# ZynQ7xxx.net
KiCad netlist of a schematic drawn in Altium Designer
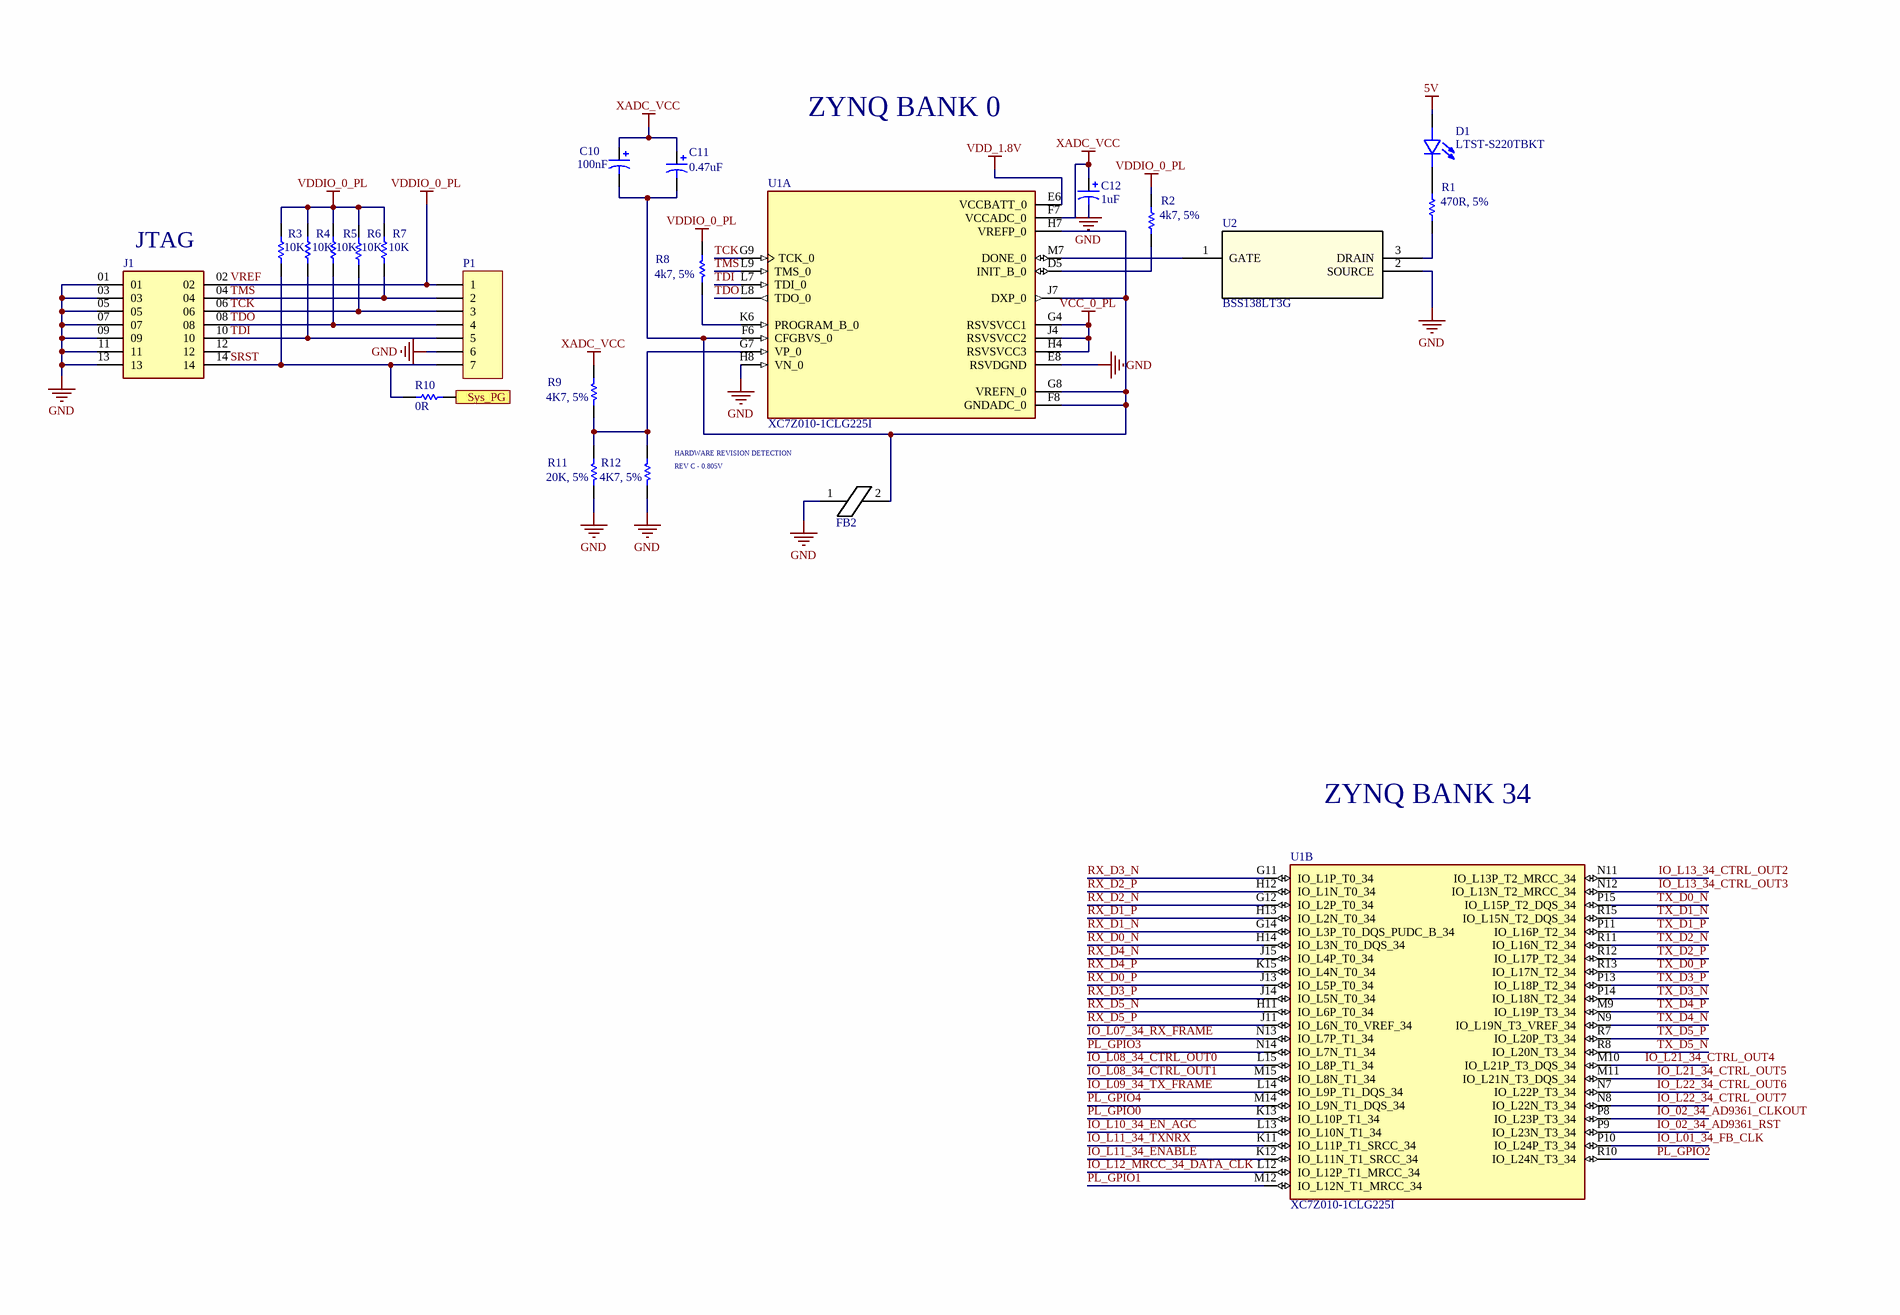
[diagram p0: ZynQ7xxx.SchDoc, top left]
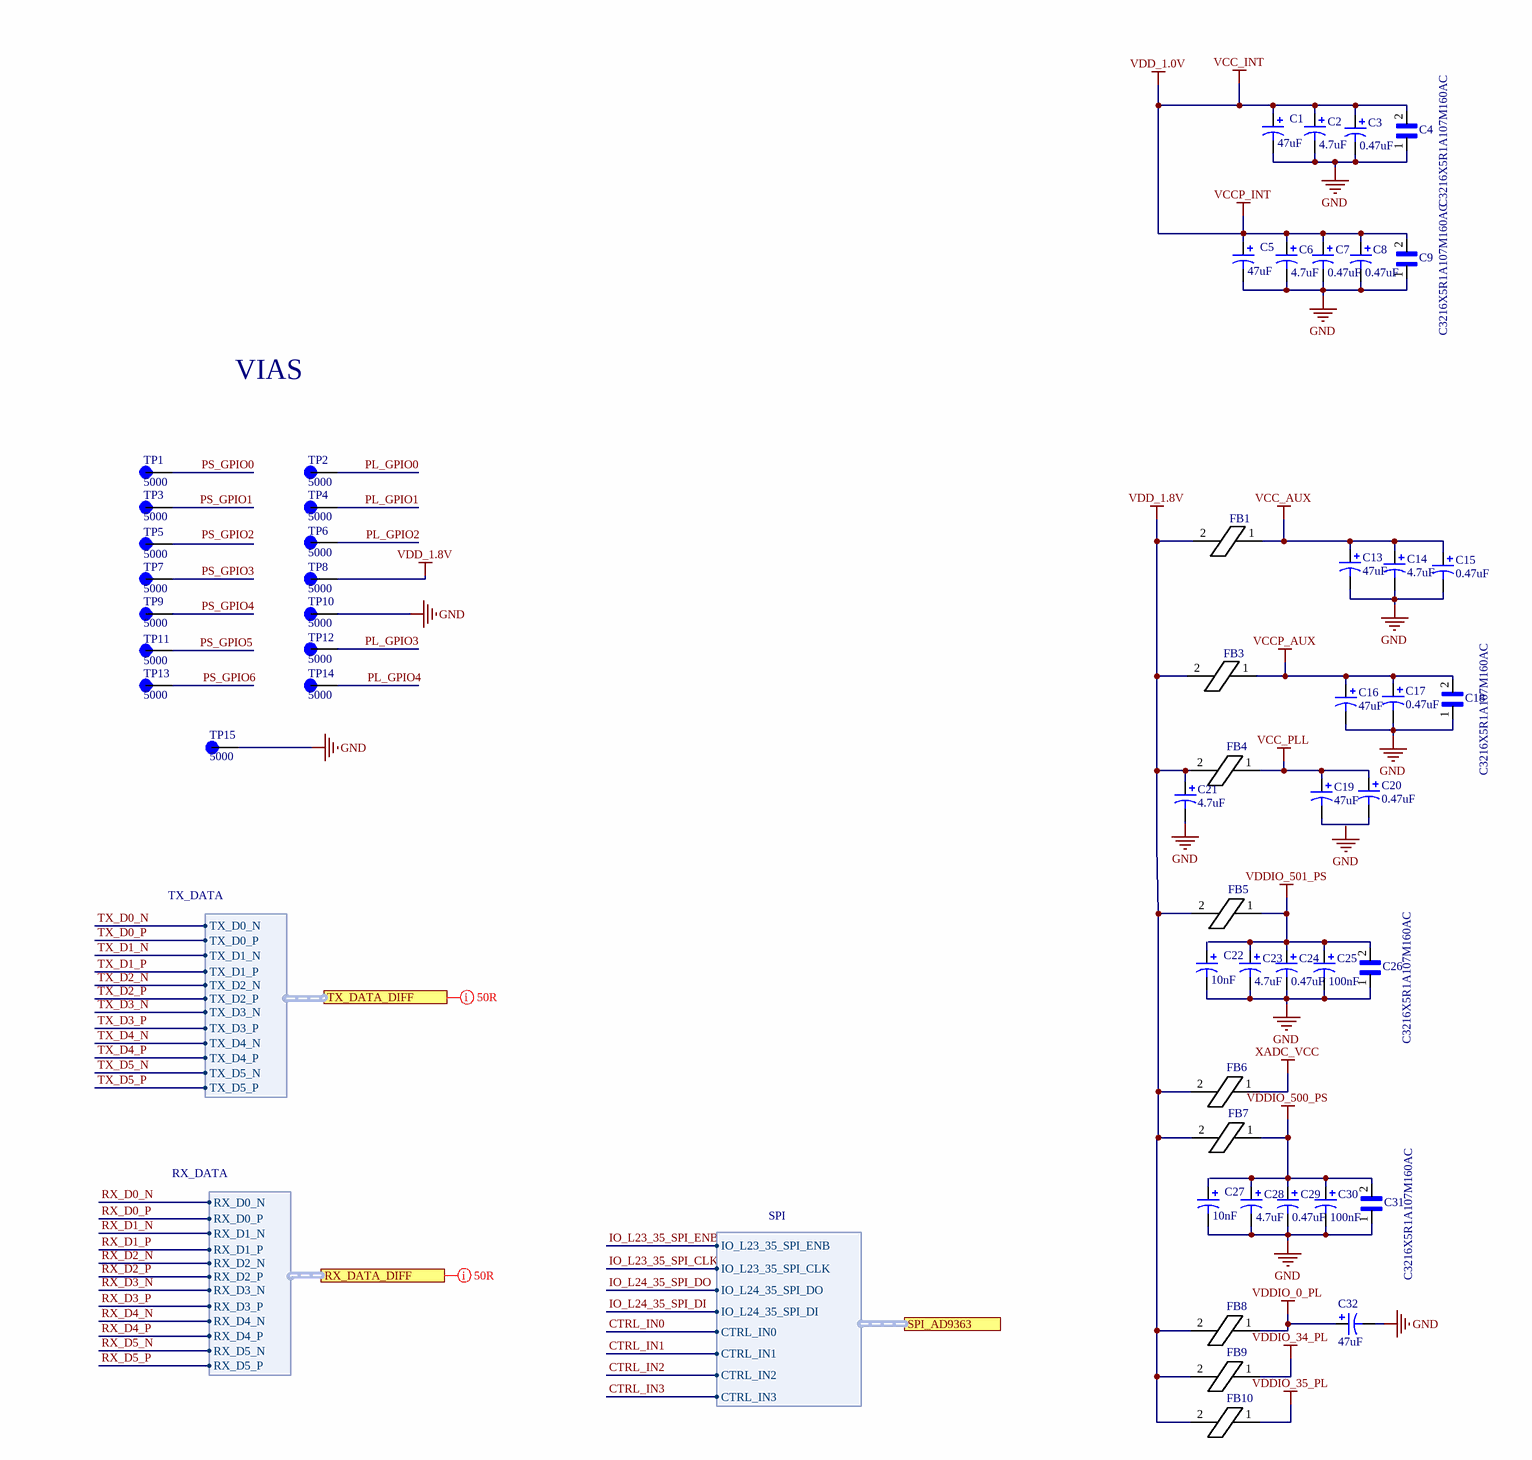
[diagram p1: ZynQ7xxx.SchDoc, top right]
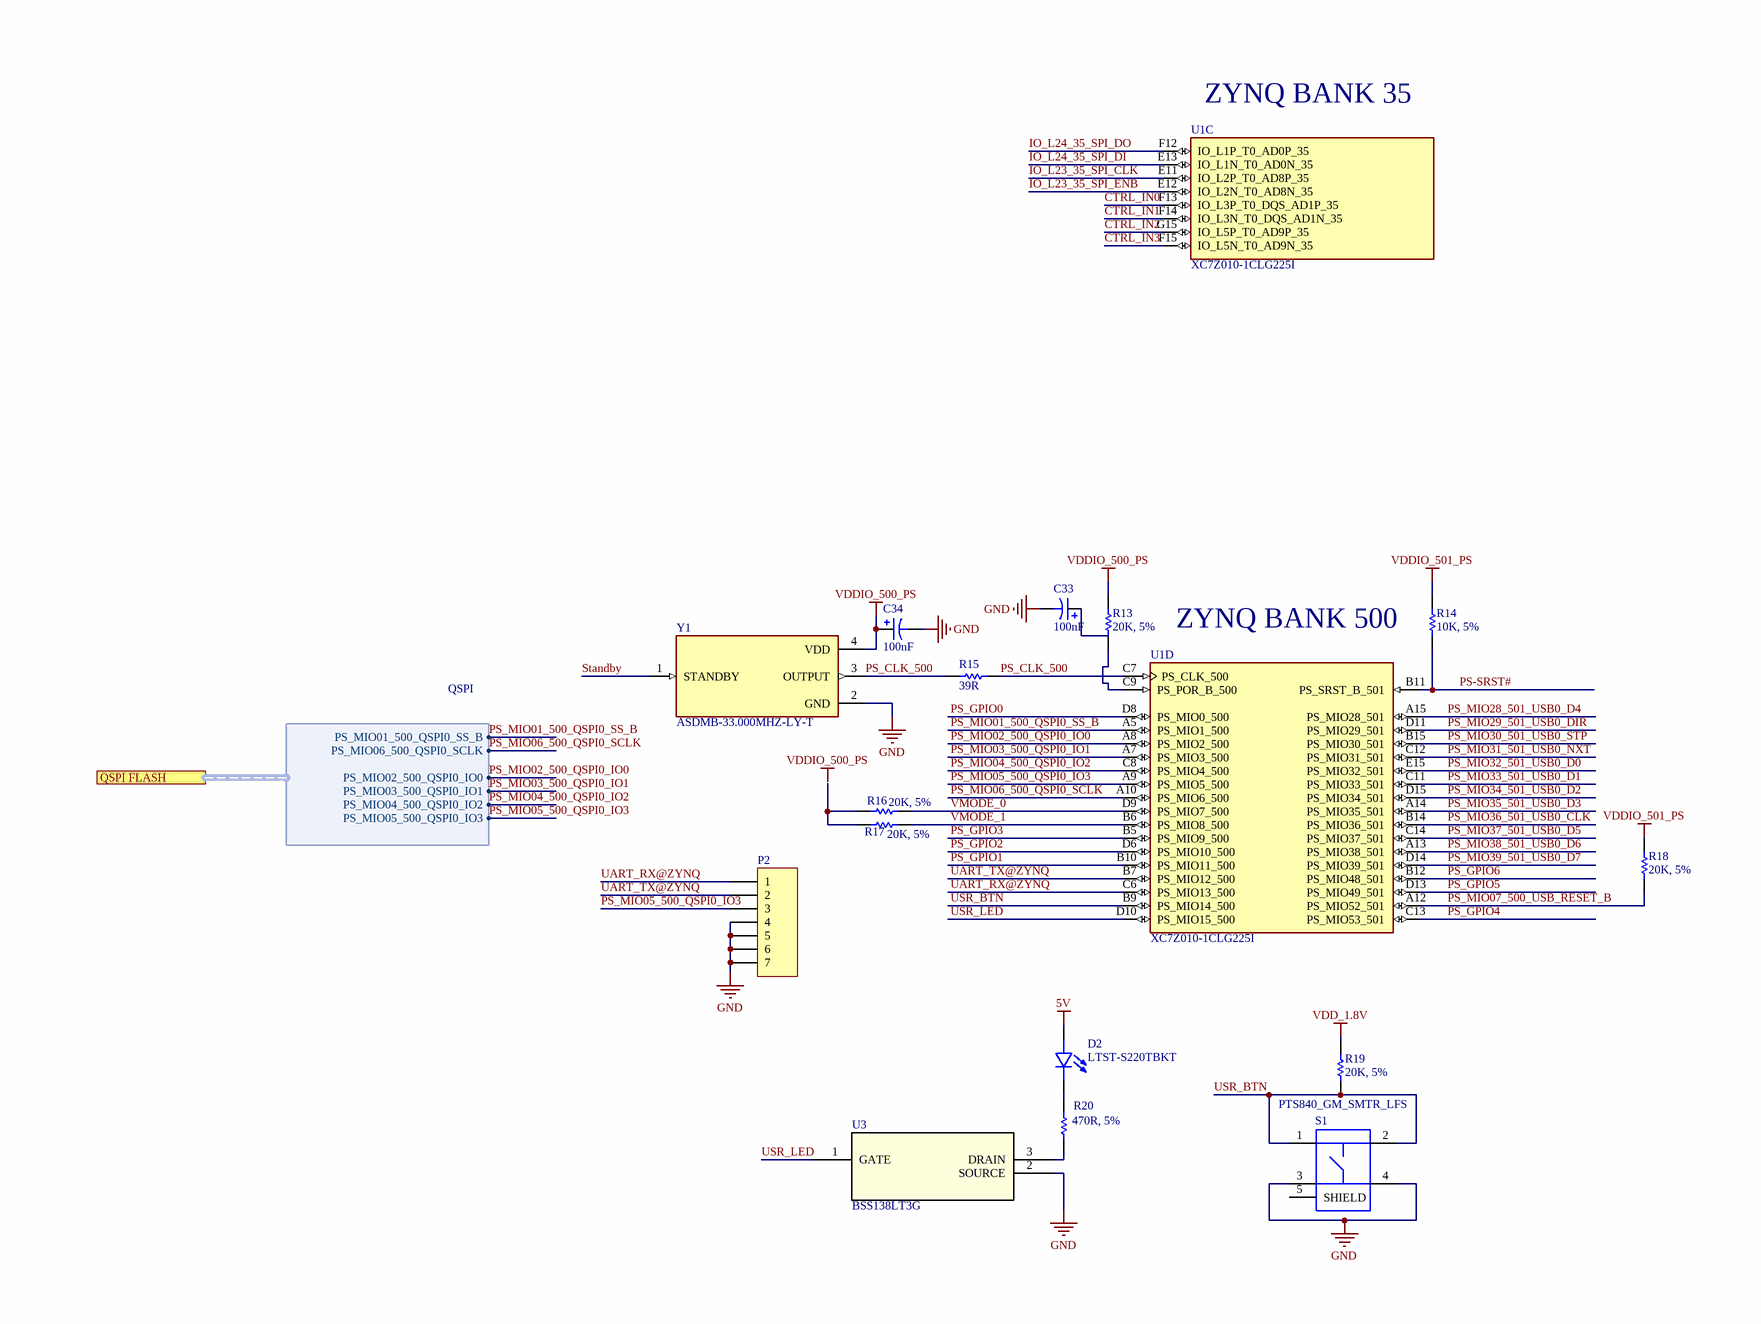
[diagram p2: ZynQ7xxx.SchDoc, bottom left]
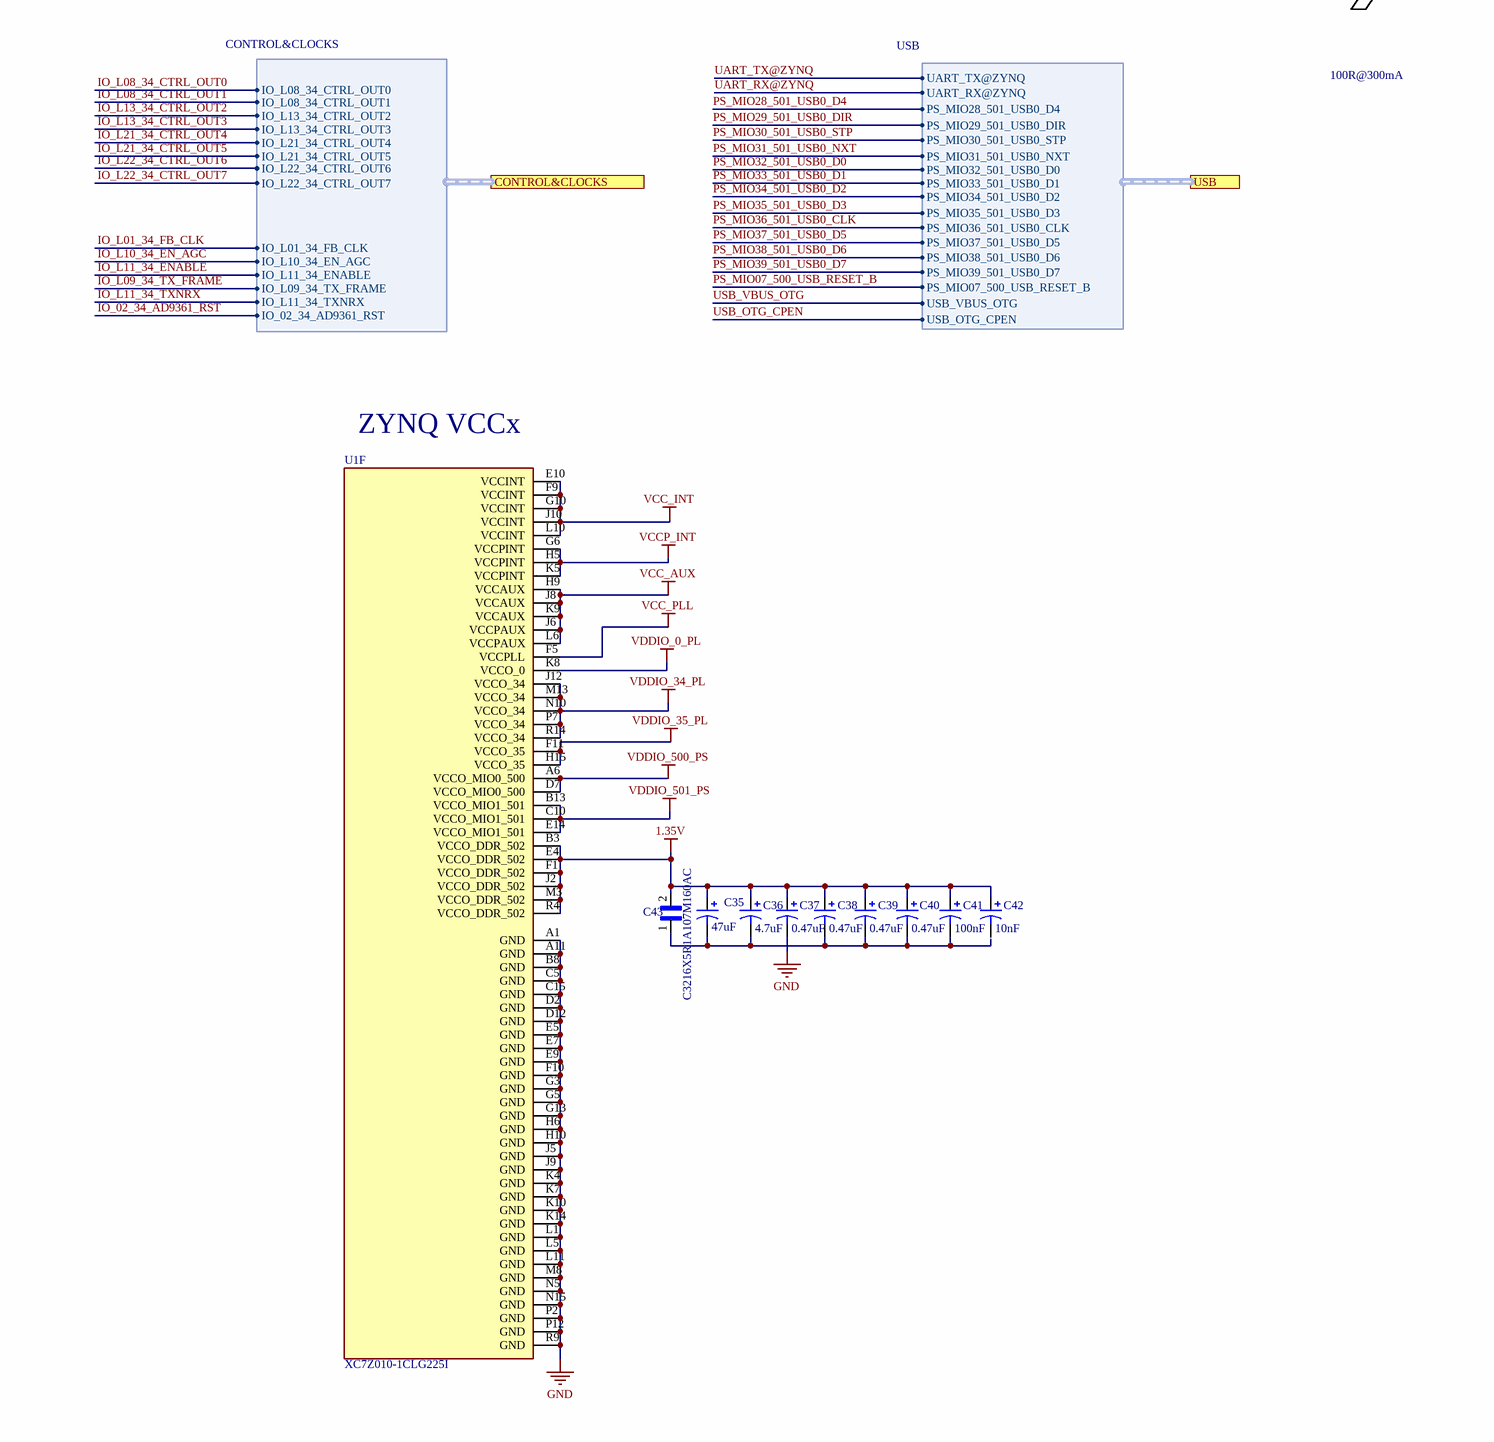
[diagram p3: ZynQ7xxx.SchDoc, bottom right]

(export (version "E")
  (design (tool "Eeschema 10.0.6"))
  (components
    (comp (ref "C1")
      (value "47uF")
      (footprint "C0805")
      (description "Polarized Capacitor (Surface Mount)")
      (fields (field (name "Comment") "Cap Pol3") (field (name "PUBLISHER") "Altium Limited"))
      (libsource (lib "Miscellaneous Devices") (part "Cap Pol3"))
    )
    (comp (ref "C2")
      (value "4.7uF")
      (footprint "C0805")
      (description "Polarized Capacitor (Surface Mount)")
      (fields (field (name "Comment") "Cap Pol3") (field (name "PUBLISHER") "Altium Limited"))
      (libsource (lib "Miscellaneous Devices") (part "Cap Pol3"))
    )
    (comp (ref "C3")
      (value "0.47uF")
      (footprint "C0805")
      (description "Polarized Capacitor (Surface Mount)")
      (fields (field (name "Comment") "Cap Pol3") (field (name "PUBLISHER") "Altium Limited"))
      (libsource (lib "Miscellaneous Devices") (part "Cap Pol3"))
    )
    (comp (ref "C4")
      (value "C3216X5R1A107M160AC")
      (footprint "CAPC3216X190N")
      (description "100 ÂµF Â±20% 10V Ceramic Capacitor X5R 1206 (3216 Metric)")
      (fields (field (name "MF") "TDK") (field (name "DIGI-KEY_PART_NUMBER") "445-6007-1-ND"))
      (libsource (lib "C3216X5R1A107M160AC") (part "C3216X5R1A107M160AC"))
    )
    (comp (ref "C5")
      (value "47uF")
      (footprint "C0805")
      (description "Polarized Capacitor (Surface Mount)")
      (fields (field (name "Comment") "Cap Pol3") (field (name "PUBLISHER") "Altium Limited"))
      (libsource (lib "Miscellaneous Devices") (part "Cap Pol3"))
    )
    (comp (ref "C6")
      (value "4.7uF")
      (footprint "C0805")
      (description "Polarized Capacitor (Surface Mount)")
      (fields (field (name "Comment") "Cap Pol3") (field (name "PUBLISHER") "Altium Limited"))
      (libsource (lib "Miscellaneous Devices") (part "Cap Pol3"))
    )
    (comp (ref "C7")
      (value "0.47uF")
      (footprint "C0805")
      (description "Polarized Capacitor (Surface Mount)")
      (fields (field (name "Comment") "Cap Pol3") (field (name "PUBLISHER") "Altium Limited"))
      (libsource (lib "Miscellaneous Devices") (part "Cap Pol3"))
    )
    (comp (ref "C8")
      (value "0.47uF")
      (footprint "C0805")
      (description "Polarized Capacitor (Surface Mount)")
      (fields (field (name "Comment") "Cap Pol3") (field (name "PUBLISHER") "Altium Limited"))
      (libsource (lib "Miscellaneous Devices") (part "Cap Pol3"))
    )
    (comp (ref "C9")
      (value "C3216X5R1A107M160AC")
      (footprint "CAPC3216X190N")
      (description "100 ÂµF Â±20% 10V Ceramic Capacitor X5R 1206 (3216 Metric)")
      (fields (field (name "MF") "TDK") (field (name "DIGI-KEY_PART_NUMBER") "445-6007-1-ND"))
      (libsource (lib "C3216X5R1A107M160AC") (part "C3216X5R1A107M160AC"))
    )
    (comp (ref "C10")
      (value "100nF")
      (footprint "C0805")
      (description "Polarized Capacitor (Surface Mount)")
      (fields (field (name "Comment") "Cap Pol3") (field (name "PUBLISHER") "Altium Limited"))
      (libsource (lib "Miscellaneous Devices") (part "Cap Pol3"))
    )
    (comp (ref "C11")
      (value "0.47uF")
      (footprint "C0805")
      (description "Polarized Capacitor (Surface Mount)")
      (fields (field (name "Comment") "Cap Pol3") (field (name "PUBLISHER") "Altium Limited"))
      (libsource (lib "Miscellaneous Devices") (part "Cap Pol3"))
    )
    (comp (ref "C12")
      (value "1uF")
      (footprint "C0805")
      (description "Polarized Capacitor (Surface Mount)")
      (fields (field (name "Comment") "Cap Pol3") (field (name "PUBLISHER") "Altium Limited"))
      (libsource (lib "Miscellaneous Devices") (part "Cap Pol3"))
    )
    (comp (ref "C13")
      (value "47uF")
      (footprint "C0805")
      (description "Polarized Capacitor (Surface Mount)")
      (fields (field (name "Comment") "Cap Pol3") (field (name "PUBLISHER") "Altium Limited"))
      (libsource (lib "Miscellaneous Devices") (part "Cap Pol3"))
    )
    (comp (ref "C14")
      (value "4.7uF")
      (footprint "C0805")
      (description "Polarized Capacitor (Surface Mount)")
      (fields (field (name "Comment") "Cap Pol3") (field (name "PUBLISHER") "Altium Limited"))
      (libsource (lib "Miscellaneous Devices") (part "Cap Pol3"))
    )
    (comp (ref "C15")
      (value "0.47uF")
      (footprint "C0805")
      (description "Polarized Capacitor (Surface Mount)")
      (fields (field (name "Comment") "Cap Pol3") (field (name "PUBLISHER") "Altium Limited"))
      (libsource (lib "Miscellaneous Devices") (part "Cap Pol3"))
    )
    (comp (ref "C16")
      (value "47uF")
      (footprint "C0805")
      (description "Polarized Capacitor (Surface Mount)")
      (fields (field (name "Comment") "Cap Pol3") (field (name "PUBLISHER") "Altium Limited"))
      (libsource (lib "Miscellaneous Devices") (part "Cap Pol3"))
    )
    (comp (ref "C17")
      (value "0.47uF")
      (footprint "C0805")
      (description "Polarized Capacitor (Surface Mount)")
      (fields (field (name "Comment") "Cap Pol3") (field (name "PUBLISHER") "Altium Limited"))
      (libsource (lib "Miscellaneous Devices") (part "Cap Pol3"))
    )
    (comp (ref "C18")
      (value "C3216X5R1A107M160AC")
      (footprint "CAPC3216X190N")
      (description "100 ÂµF Â±20% 10V Ceramic Capacitor X5R 1206 (3216 Metric)")
      (fields (field (name "MF") "TDK") (field (name "DIGI-KEY_PART_NUMBER") "445-6007-1-ND"))
      (libsource (lib "C3216X5R1A107M160AC") (part "C3216X5R1A107M160AC"))
    )
    (comp (ref "C19")
      (value "47uF")
      (footprint "C0805")
      (description "Polarized Capacitor (Surface Mount)")
      (fields (field (name "Comment") "Cap Pol3") (field (name "PUBLISHER") "Altium Limited"))
      (libsource (lib "Miscellaneous Devices") (part "Cap Pol3"))
    )
    (comp (ref "C20")
      (value "0.47uF")
      (footprint "C0805")
      (description "Polarized Capacitor (Surface Mount)")
      (fields (field (name "Comment") "Cap Pol3") (field (name "PUBLISHER") "Altium Limited"))
      (libsource (lib "Miscellaneous Devices") (part "Cap Pol3"))
    )
    (comp (ref "C21")
      (value "4.7uF")
      (footprint "C0805")
      (description "Polarized Capacitor (Surface Mount)")
      (fields (field (name "Comment") "Cap Pol3") (field (name "PUBLISHER") "Altium Limited"))
      (libsource (lib "Miscellaneous Devices") (part "Cap Pol3"))
    )
    (comp (ref "C22")
      (value "10nF")
      (footprint "C0805")
      (description "Polarized Capacitor (Surface Mount)")
      (fields (field (name "Comment") "Cap Pol3") (field (name "PUBLISHER") "Altium Limited"))
      (libsource (lib "Miscellaneous Devices") (part "Cap Pol3"))
    )
    (comp (ref "C23")
      (value "4.7uF")
      (footprint "C0805")
      (description "Polarized Capacitor (Surface Mount)")
      (fields (field (name "Comment") "Cap Pol3") (field (name "PUBLISHER") "Altium Limited"))
      (libsource (lib "Miscellaneous Devices") (part "Cap Pol3"))
    )
    (comp (ref "C24")
      (value "0.47uF")
      (footprint "C0805")
      (description "Polarized Capacitor (Surface Mount)")
      (fields (field (name "Comment") "Cap Pol3") (field (name "PUBLISHER") "Altium Limited"))
      (libsource (lib "Miscellaneous Devices") (part "Cap Pol3"))
    )
    (comp (ref "C25")
      (value "100nF")
      (footprint "C0805")
      (description "Polarized Capacitor (Surface Mount)")
      (fields (field (name "Comment") "Cap Pol3") (field (name "PUBLISHER") "Altium Limited"))
      (libsource (lib "Miscellaneous Devices") (part "Cap Pol3"))
    )
    (comp (ref "C26")
      (value "C3216X5R1A107M160AC")
      (footprint "CAPC3216X190N")
      (description "100 ÂµF Â±20% 10V Ceramic Capacitor X5R 1206 (3216 Metric)")
      (fields (field (name "MF") "TDK") (field (name "DIGI-KEY_PART_NUMBER") "445-6007-1-ND"))
      (libsource (lib "C3216X5R1A107M160AC") (part "C3216X5R1A107M160AC"))
    )
    (comp (ref "C27")
      (value "10nF")
      (footprint "C0805")
      (description "Polarized Capacitor (Surface Mount)")
      (fields (field (name "Comment") "Cap Pol3") (field (name "PUBLISHER") "Altium Limited"))
      (libsource (lib "Miscellaneous Devices") (part "Cap Pol3"))
    )
    (comp (ref "C28")
      (value "4.7uF")
      (footprint "C0805")
      (description "Polarized Capacitor (Surface Mount)")
      (fields (field (name "Comment") "Cap Pol3") (field (name "PUBLISHER") "Altium Limited"))
      (libsource (lib "Miscellaneous Devices") (part "Cap Pol3"))
    )
    (comp (ref "C29")
      (value "0.47uF")
      (footprint "C0805")
      (description "Polarized Capacitor (Surface Mount)")
      (fields (field (name "Comment") "Cap Pol3") (field (name "PUBLISHER") "Altium Limited"))
      (libsource (lib "Miscellaneous Devices") (part "Cap Pol3"))
    )
    (comp (ref "C30")
      (value "100nF")
      (footprint "C0805")
      (description "Polarized Capacitor (Surface Mount)")
      (fields (field (name "Comment") "Cap Pol3") (field (name "PUBLISHER") "Altium Limited"))
      (libsource (lib "Miscellaneous Devices") (part "Cap Pol3"))
    )
    (comp (ref "C31")
      (value "C3216X5R1A107M160AC")
      (footprint "CAPC3216X190N")
      (description "100 ÂµF Â±20% 10V Ceramic Capacitor X5R 1206 (3216 Metric)")
      (fields (field (name "MF") "TDK") (field (name "DIGI-KEY_PART_NUMBER") "445-6007-1-ND"))
      (libsource (lib "C3216X5R1A107M160AC") (part "C3216X5R1A107M160AC"))
    )
    (comp (ref "C32")
      (value "47uF")
      (footprint "C0805")
      (description "Polarized Capacitor (Surface Mount)")
      (fields (field (name "Comment") "Cap Pol3") (field (name "PUBLISHER") "Altium Limited"))
      (libsource (lib "Miscellaneous Devices") (part "Cap Pol3"))
    )
    (comp (ref "C33")
      (value "100nF")
      (footprint "C0805")
      (description "Polarized Capacitor (Surface Mount)")
      (fields (field (name "Comment") "Cap Pol3") (field (name "PUBLISHER") "Altium Limited"))
      (libsource (lib "Miscellaneous Devices") (part "Cap Pol3"))
    )
    (comp (ref "C34")
      (value "100nF")
      (footprint "C0805")
      (description "Polarized Capacitor (Surface Mount)")
      (fields (field (name "Comment") "Cap Pol3") (field (name "PUBLISHER") "Altium Limited"))
      (libsource (lib "Miscellaneous Devices") (part "Cap Pol3"))
    )
    (comp (ref "C35")
      (value "47uF")
      (footprint "C0805")
      (description "Polarized Capacitor (Surface Mount)")
      (fields (field (name "Comment") "Cap Pol3") (field (name "PUBLISHER") "Altium Limited"))
      (libsource (lib "Miscellaneous Devices") (part "Cap Pol3"))
    )
    (comp (ref "C36")
      (value "4.7uF")
      (footprint "C0805")
      (description "Polarized Capacitor (Surface Mount)")
      (fields (field (name "Comment") "Cap Pol3") (field (name "PUBLISHER") "Altium Limited"))
      (libsource (lib "Miscellaneous Devices") (part "Cap Pol3"))
    )
    (comp (ref "C37")
      (value "0.47uF")
      (footprint "C0805")
      (description "Polarized Capacitor (Surface Mount)")
      (fields (field (name "Comment") "Cap Pol3") (field (name "PUBLISHER") "Altium Limited"))
      (libsource (lib "Miscellaneous Devices") (part "Cap Pol3"))
    )
    (comp (ref "C38")
      (value "0.47uF")
      (footprint "C0805")
      (description "Polarized Capacitor (Surface Mount)")
      (fields (field (name "Comment") "Cap Pol3") (field (name "PUBLISHER") "Altium Limited"))
      (libsource (lib "Miscellaneous Devices") (part "Cap Pol3"))
    )
    (comp (ref "C39")
      (value "0.47uF")
      (footprint "C0805")
      (description "Polarized Capacitor (Surface Mount)")
      (fields (field (name "Comment") "Cap Pol3") (field (name "PUBLISHER") "Altium Limited"))
      (libsource (lib "Miscellaneous Devices") (part "Cap Pol3"))
    )
    (comp (ref "C40")
      (value "0.47uF")
      (footprint "C0805")
      (description "Polarized Capacitor (Surface Mount)")
      (fields (field (name "Comment") "Cap Pol3") (field (name "PUBLISHER") "Altium Limited"))
      (libsource (lib "Miscellaneous Devices") (part "Cap Pol3"))
    )
    (comp (ref "C41")
      (value "100nF")
      (footprint "C0805")
      (description "Polarized Capacitor (Surface Mount)")
      (fields (field (name "Comment") "Cap Pol3") (field (name "PUBLISHER") "Altium Limited"))
      (libsource (lib "Miscellaneous Devices") (part "Cap Pol3"))
    )
    (comp (ref "C42")
      (value "10nF")
      (footprint "C0805")
      (description "Polarized Capacitor (Surface Mount)")
      (fields (field (name "Comment") "Cap Pol3") (field (name "PUBLISHER") "Altium Limited"))
      (libsource (lib "Miscellaneous Devices") (part "Cap Pol3"))
    )
    (comp (ref "C43")
      (value "C3216X5R1A107M160AC")
      (footprint "CAPC3216X190N")
      (description "100 ÂµF Â±20% 10V Ceramic Capacitor X5R 1206 (3216 Metric)")
      (fields (field (name "MF") "TDK") (field (name "DIGI-KEY_PART_NUMBER") "445-6007-1-ND"))
      (libsource (lib "C3216X5R1A107M160AC") (part "C3216X5R1A107M160AC"))
    )
    (comp (ref "D1")
      (value "LTST-S220TBKT")
      (footprint "LED_LTST-S220TBKT")
      (libsource (lib "LTST-S220TBKT") (part "LTST-S220TBKT"))
    )
    (comp (ref "D2")
      (value "LTST-S220TBKT")
      (footprint "LED_LTST-S220TBKT")
      (libsource (lib "LTST-S220TBKT") (part "LTST-S220TBKT"))
    )
    (comp (ref "FB1")
      (value "FERRITA")
      (footprint "0805R")
      (libsource (lib "lib_protel_HC") (part "FERRITA"))
    )
    (comp (ref "FB2")
      (value "FERRITA")
      (footprint "0805R")
      (libsource (lib "lib_protel_HC") (part "FERRITA"))
    )
    (comp (ref "FB3")
      (value "FERRITA")
      (footprint "0805R")
      (libsource (lib "lib_protel_HC") (part "FERRITA"))
    )
    (comp (ref "FB4")
      (value "FERRITA")
      (footprint "0805R")
      (libsource (lib "lib_protel_HC") (part "FERRITA"))
    )
    (comp (ref "FB5")
      (value "FERRITA")
      (footprint "0805R")
      (libsource (lib "lib_protel_HC") (part "FERRITA"))
    )
    (comp (ref "FB6")
      (value "FERRITA")
      (footprint "0805R")
      (libsource (lib "lib_protel_HC") (part "FERRITA"))
    )
    (comp (ref "FB7")
      (value "FERRITA")
      (footprint "0805R")
      (libsource (lib "lib_protel_HC") (part "FERRITA"))
    )
    (comp (ref "FB8")
      (value "FERRITA")
      (footprint "0805R")
      (libsource (lib "lib_protel_HC") (part "FERRITA"))
    )
    (comp (ref "FB9")
      (value "FERRITA")
      (footprint "0805R")
      (libsource (lib "lib_protel_HC") (part "FERRITA"))
    )
    (comp (ref "FB10")
      (value "FERRITA")
      (footprint "0805R")
      (libsource (lib "lib_protel_HC") (part "FERRITA"))
    )
    (comp (ref "J1")
      (value "MTMM-107-03-G-D-190")
      (footprint "SAMTEC_MTMM-107-03-G-D-190")
      (libsource (lib "MTMM-107-03-G-D-190") (part "MTMM-107-03-G-D-190"))
    )
    (comp (ref "P1")
      (value "Header 7")
      (footprint "HDR1X7")
      (description "Header, 7-Pin")
      (fields (field (name "PUBLISHER") "Altium Limited"))
      (libsource (lib "Miscellaneous Connectors") (part "Header 7"))
    )
    (comp (ref "P2")
      (value "Header 7")
      (footprint "HDR1X7")
      (description "Header, 7-Pin")
      (fields (field (name "PUBLISHER") "Altium Limited"))
      (libsource (lib "Miscellaneous Connectors") (part "Header 7"))
    )
    (comp (ref "R1")
      (value "470R, 5%")
      (footprint "0603")
      (description "Resistor")
      (fields
        (field (name "MANUFACTURER") "Generic Components")
        (field (name "Comment") "Res1")
        (field (name "PUBLISHER") "Altium Limited")
      )
      (libsource (lib "lib_protel_HC") (part "Res1_1"))
    )
    (comp (ref "R2")
      (value "4k7, 5%")
      (footprint "0603")
      (description "Resistor")
      (fields
        (field (name "MANUFACTURER") "Generic Components")
        (field (name "Comment") "Res1")
        (field (name "PUBLISHER") "Altium Limited")
      )
      (libsource (lib "lib_protel_HC") (part "Res1_1"))
    )
    (comp (ref "R3")
      (value "10K")
      (footprint "0603")
      (description "Resistor")
      (fields
        (field (name "MANUFACTURER") "Generic Components")
        (field (name "Comment") "Res1")
        (field (name "PUBLISHER") "Altium Limited")
      )
      (libsource (lib "lib_protel_HC") (part "Res1_1"))
    )
    (comp (ref "R4")
      (value "10K")
      (footprint "0603")
      (description "Resistor")
      (fields
        (field (name "MANUFACTURER") "Generic Components")
        (field (name "Comment") "Res1")
        (field (name "PUBLISHER") "Altium Limited")
      )
      (libsource (lib "lib_protel_HC") (part "Res1_1"))
    )
    (comp (ref "R5")
      (value "10K")
      (footprint "0603")
      (description "Resistor")
      (fields
        (field (name "MANUFACTURER") "Generic Components")
        (field (name "Comment") "Res1")
        (field (name "PUBLISHER") "Altium Limited")
      )
      (libsource (lib "lib_protel_HC") (part "Res1_1"))
    )
    (comp (ref "R6")
      (value "10K")
      (footprint "0603")
      (description "Resistor")
      (fields
        (field (name "MANUFACTURER") "Generic Components")
        (field (name "Comment") "Res1")
        (field (name "PUBLISHER") "Altium Limited")
      )
      (libsource (lib "lib_protel_HC") (part "Res1_1"))
    )
    (comp (ref "R7")
      (value "10K")
      (footprint "0603")
      (description "Resistor")
      (fields
        (field (name "MANUFACTURER") "Generic Components")
        (field (name "Comment") "Res1")
        (field (name "PUBLISHER") "Altium Limited")
      )
      (libsource (lib "lib_protel_HC") (part "Res1_1"))
    )
    (comp (ref "R8")
      (value "4k7, 5%")
      (footprint "0603")
      (description "Resistor")
      (fields
        (field (name "MANUFACTURER") "Generic Components")
        (field (name "Comment") "Res1")
        (field (name "PUBLISHER") "Altium Limited")
      )
      (libsource (lib "lib_protel_HC") (part "Res1_1"))
    )
    (comp (ref "R9")
      (value "4K7, 5%")
      (footprint "0603")
      (description "Resistor")
      (fields
        (field (name "MANUFACTURER") "Generic Components")
        (field (name "Comment") "Res1")
        (field (name "PUBLISHER") "Altium Limited")
      )
      (libsource (lib "lib_protel_HC") (part "Res1_1"))
    )
    (comp (ref "R10")
      (value "0R")
      (footprint "0603")
      (description "Resistor")
      (fields
        (field (name "MANUFACTURER") "Generic Components")
        (field (name "Comment") "Res1")
        (field (name "PUBLISHER") "Altium Limited")
      )
      (libsource (lib "lib_protel_HC") (part "Res1_1"))
    )
    (comp (ref "R11")
      (value "20K, 5%")
      (footprint "0603")
      (description "Resistor")
      (fields
        (field (name "MANUFACTURER") "Generic Components")
        (field (name "Comment") "Res1")
        (field (name "PUBLISHER") "Altium Limited")
      )
      (libsource (lib "lib_protel_HC") (part "Res1_1"))
    )
    (comp (ref "R12")
      (value "4K7, 5%")
      (footprint "0603")
      (description "Resistor")
      (fields
        (field (name "MANUFACTURER") "Generic Components")
        (field (name "Comment") "Res1")
        (field (name "PUBLISHER") "Altium Limited")
      )
      (libsource (lib "lib_protel_HC") (part "Res1_1"))
    )
    (comp (ref "R13")
      (value "20K, 5%")
      (footprint "0603")
      (description "Resistor")
      (fields
        (field (name "MANUFACTURER") "Generic Components")
        (field (name "Comment") "Res1")
        (field (name "PUBLISHER") "Altium Limited")
      )
      (libsource (lib "lib_protel_HC") (part "Res1_1"))
    )
    (comp (ref "R14")
      (value "10K, 5%")
      (footprint "0603")
      (description "Resistor")
      (fields
        (field (name "MANUFACTURER") "Generic Components")
        (field (name "Comment") "Res1")
        (field (name "PUBLISHER") "Altium Limited")
      )
      (libsource (lib "lib_protel_HC") (part "Res1_1"))
    )
    (comp (ref "R15")
      (value "39R")
      (footprint "0603")
      (description "Resistor")
      (fields
        (field (name "MANUFACTURER") "Generic Components")
        (field (name "Comment") "Res1")
        (field (name "PUBLISHER") "Altium Limited")
      )
      (libsource (lib "lib_protel_HC") (part "Res1_1"))
    )
    (comp (ref "R16")
      (value "20K, 5%")
      (footprint "0603")
      (description "Resistor")
      (fields
        (field (name "MANUFACTURER") "Generic Components")
        (field (name "Comment") "Res1")
        (field (name "PUBLISHER") "Altium Limited")
      )
      (libsource (lib "lib_protel_HC") (part "Res1_1"))
    )
    (comp (ref "R17")
      (value "20K, 5%")
      (footprint "0603")
      (description "Resistor")
      (fields
        (field (name "MANUFACTURER") "Generic Components")
        (field (name "Comment") "Res1")
        (field (name "PUBLISHER") "Altium Limited")
      )
      (libsource (lib "lib_protel_HC") (part "Res1_1"))
    )
    (comp (ref "R18")
      (value "20K, 5%")
      (footprint "0603")
      (description "Resistor")
      (fields
        (field (name "MANUFACTURER") "Generic Components")
        (field (name "Comment") "Res1")
        (field (name "PUBLISHER") "Altium Limited")
      )
      (libsource (lib "lib_protel_HC") (part "Res1_1"))
    )
    (comp (ref "R19")
      (value "20K, 5%")
      (footprint "0603")
      (description "Resistor")
      (fields
        (field (name "MANUFACTURER") "Generic Components")
        (field (name "Comment") "Res1")
        (field (name "PUBLISHER") "Altium Limited")
      )
      (libsource (lib "lib_protel_HC") (part "Res1_1"))
    )
    (comp (ref "R20")
      (value "470R, 5%")
      (footprint "0603")
      (description "Resistor")
      (fields
        (field (name "MANUFACTURER") "Generic Components")
        (field (name "Comment") "Res1")
        (field (name "PUBLISHER") "Altium Limited")
      )
      (libsource (lib "lib_protel_HC") (part "Res1_1"))
    )
    (comp (ref "S1")
      (value "PTS840_GM_SMTR_LFS")
      (footprint "SW_PTS840GMSMTRLFS")
      (description "Tactile Switch SPST-NO Side Actuated Surface Mount, Right Angle")
      (fields (field (name "MP") "PTS840 GM SMTR LFS") (field (name "MF") "C&K"))
      (libsource (lib "PTS840_GM_SMTR_LFS") (part "PTS840_GM_SMTR_LFS"))
    )
    (comp (ref "TP1")
      (value "5000")
      (footprint "KEYSTONE_5000")
      (fields (field (name "MF") "Keystone Electronics"))
      (libsource (lib "5000") (part "5000"))
    )
    (comp (ref "TP2")
      (value "5000")
      (footprint "KEYSTONE_5000")
      (fields (field (name "MF") "Keystone Electronics"))
      (libsource (lib "5000") (part "5000"))
    )
    (comp (ref "TP3")
      (value "5000")
      (footprint "KEYSTONE_5000")
      (fields (field (name "MF") "Keystone Electronics"))
      (libsource (lib "5000") (part "5000"))
    )
    (comp (ref "TP4")
      (value "5000")
      (footprint "KEYSTONE_5000")
      (fields (field (name "MF") "Keystone Electronics"))
      (libsource (lib "5000") (part "5000"))
    )
    (comp (ref "TP5")
      (value "5000")
      (footprint "KEYSTONE_5000")
      (fields (field (name "MF") "Keystone Electronics"))
      (libsource (lib "5000") (part "5000"))
    )
    (comp (ref "TP6")
      (value "5000")
      (footprint "KEYSTONE_5000")
      (fields (field (name "MF") "Keystone Electronics"))
      (libsource (lib "5000") (part "5000"))
    )
    (comp (ref "TP7")
      (value "5000")
      (footprint "KEYSTONE_5000")
      (fields (field (name "MF") "Keystone Electronics"))
      (libsource (lib "5000") (part "5000"))
    )
    (comp (ref "TP8")
      (value "5000")
      (footprint "KEYSTONE_5000")
      (fields (field (name "MF") "Keystone Electronics"))
      (libsource (lib "5000") (part "5000"))
    )
    (comp (ref "TP9")
      (value "5000")
      (footprint "KEYSTONE_5000")
      (fields (field (name "MF") "Keystone Electronics"))
      (libsource (lib "5000") (part "5000"))
    )
    (comp (ref "TP10")
      (value "5000")
      (footprint "KEYSTONE_5000")
      (fields (field (name "MF") "Keystone Electronics"))
      (libsource (lib "5000") (part "5000"))
    )
    (comp (ref "TP11")
      (value "5000")
      (footprint "KEYSTONE_5000")
      (fields (field (name "MF") "Keystone Electronics"))
      (libsource (lib "5000") (part "5000"))
    )
    (comp (ref "TP12")
      (value "5000")
      (footprint "KEYSTONE_5000")
      (fields (field (name "MF") "Keystone Electronics"))
      (libsource (lib "5000") (part "5000"))
    )
    (comp (ref "TP13")
      (value "5000")
      (footprint "KEYSTONE_5000")
      (fields (field (name "MF") "Keystone Electronics"))
      (libsource (lib "5000") (part "5000"))
    )
    (comp (ref "TP14")
      (value "5000")
      (footprint "KEYSTONE_5000")
      (fields (field (name "MF") "Keystone Electronics"))
      (libsource (lib "5000") (part "5000"))
    )
    (comp (ref "TP15")
      (value "5000")
      (footprint "KEYSTONE_5000")
      (fields (field (name "MF") "Keystone Electronics"))
      (libsource (lib "5000") (part "5000"))
    )
    (comp (ref "U1")
      (value "XC7Z010-1CLG225I")
      (footprint "BGA225C80P15X15_1300X1300X150N")
      (fields (field (name "MF") "Xilinx Inc."))
      (libsource (lib "XC7Z010-1CLG225I") (part "XC7Z010-1CLG225I"))
    )
    (comp (ref "U2")
      (value "BSS138LT3G")
      (footprint "SOT-23-3_1P4X3P040_ONS")
      (description "No Description Available")
      (libsource (lib "BSS138LT3G") (part "BSS138LT3G"))
    )
    (comp (ref "U3")
      (value "BSS138LT3G")
      (footprint "SOT-23-3_1P4X3P040_ONS")
      (description "No Description Available")
      (libsource (lib "BSS138LT3G") (part "BSS138LT3G"))
    )
    (comp (ref "Y1")
      (value "ASDMB-33.000MHZ-LY-T")
      (footprint "XTAL_ASDMB-33.000MHZ-LY-T")
      (libsource (lib "ASDMB-33.000MHZ-LY-T") (part "ASDMB-33.000MHZ-LY-T"))
    )
  )
  (nets
    (net (code "7") (name "/CTRL_IN0") (class "Default")
      (node (ref "U1") (pin "F13") (pinfunction "IO_L3P_T0_DQS_AD1P_35_F13") (pintype "bidirectional"))
    )
    (net (code "8") (name "/CTRL_IN1") (class "Default")
      (node (ref "U1") (pin "F14") (pinfunction "IO_L3N_T0_DQS_AD1N_35_F14") (pintype "bidirectional"))
    )
    (net (code "9") (name "/CTRL_IN2") (class "Default")
      (node (ref "U1") (pin "G15") (pinfunction "IO_L5P_T0_AD9P_35_G15") (pintype "bidirectional"))
    )
    (net (code "10") (name "/CTRL_IN3") (class "Default")
      (node (ref "U1") (pin "F15") (pinfunction "IO_L5N_T0_AD9N_35_F15") (pintype "bidirectional"))
    )
    (net (code "11") (name "/IO_02_34_AD9361_CLKOUT") (class "Default")
      (node (ref "U1") (pin "P8") (pinfunction "IO_L23P_T3_34_P8") (pintype "bidirectional"))
    )
    (net (code "12") (name "/IO_02_34_AD9361_RST") (class "Default")
      (node (ref "U1") (pin "P9") (pinfunction "IO_L23N_T3_34_P9") (pintype "bidirectional"))
    )
    (net (code "13") (name "/IO_L01_34_FB_CLK") (class "Default")
      (node (ref "U1") (pin "P10") (pinfunction "IO_L24P_T3_34_P10") (pintype "bidirectional"))
    )
    (net (code "14") (name "/IO_L07_34_RX_FRAME") (class "Default")
      (node (ref "U1") (pin "N13") (pinfunction "IO_L7P_T1_34_N13") (pintype "bidirectional"))
    )
    (net (code "15") (name "/IO_L08_34_CTRL_OUT0") (class "Default")
      (node (ref "U1") (pin "L15") (pinfunction "IO_L8P_T1_34_L15") (pintype "bidirectional"))
    )
    (net (code "16") (name "/IO_L08_34_CTRL_OUT1") (class "Default")
      (node (ref "U1") (pin "M15") (pinfunction "IO_L8N_T1_34_M15") (pintype "bidirectional"))
    )
    (net (code "17") (name "/IO_L09_34_TX_FRAME") (class "Default")
      (node (ref "U1") (pin "L14") (pinfunction "IO_L9P_T1_DQS_34_L14") (pintype "bidirectional"))
    )
    (net (code "18") (name "/IO_L10_34_EN_AGC") (class "Default")
      (node (ref "U1") (pin "L13") (pinfunction "IO_L10N_T1_34_L13") (pintype "bidirectional"))
    )
    (net (code "19") (name "/IO_L11_34_ENABLE") (class "Default")
      (node (ref "U1") (pin "K12") (pinfunction "IO_L11N_T1_SRCC_34_K12") (pintype "bidirectional"))
    )
    (net (code "20") (name "/IO_L11_34_TXNRX") (class "Default")
      (node (ref "U1") (pin "K11") (pinfunction "IO_L11P_T1_SRCC_34_K11") (pintype "bidirectional"))
    )
    (net (code "21") (name "/IO_L12_MRCC_34_DATA_CLK") (class "Default")
      (node (ref "U1") (pin "L12") (pinfunction "IO_L12P_T1_MRCC_34_L12") (pintype "bidirectional"))
    )
    (net (code "22") (name "/IO_L13_34_CTRL_OUT2") (class "Default")
      (node (ref "U1") (pin "N11") (pinfunction "IO_L13P_T2_MRCC_34_N11") (pintype "bidirectional"))
    )
    (net (code "23") (name "/IO_L13_34_CTRL_OUT3") (class "Default")
      (node (ref "U1") (pin "N12") (pinfunction "IO_L13N_T2_MRCC_34_N12") (pintype "bidirectional"))
    )
    (net (code "24") (name "/IO_L21_34_CTRL_OUT4") (class "Default")
      (node (ref "U1") (pin "M10") (pinfunction "IO_L21P_T3_DQS_34_M10") (pintype "bidirectional"))
    )
    (net (code "25") (name "/IO_L21_34_CTRL_OUT5") (class "Default")
      (node (ref "U1") (pin "M11") (pinfunction "IO_L21N_T3_DQS_34_M11") (pintype "bidirectional"))
    )
    (net (code "26") (name "/IO_L22_34_CTRL_OUT6") (class "Default")
      (node (ref "U1") (pin "N7") (pinfunction "IO_L22P_T3_34_N7") (pintype "bidirectional"))
    )
    (net (code "27") (name "/IO_L22_34_CTRL_OUT7") (class "Default")
      (node (ref "U1") (pin "N8") (pinfunction "IO_L22N_T3_34_N8") (pintype "bidirectional"))
    )
    (net (code "28") (name "/IO_L23_35_SPI_CLK") (class "Default")
      (node (ref "U1") (pin "E11") (pinfunction "IO_L2P_T0_AD8P_35_E11") (pintype "bidirectional"))
    )
    (net (code "29") (name "/IO_L23_35_SPI_ENB") (class "Default")
      (node (ref "U1") (pin "E12") (pinfunction "IO_L2N_T0_AD8N_35_E12") (pintype "bidirectional"))
    )
    (net (code "30") (name "/IO_L24_35_SPI_DI") (class "Default")
      (node (ref "U1") (pin "E13") (pinfunction "IO_L1N_T0_AD0N_35_E13") (pintype "bidirectional"))
    )
    (net (code "31") (name "/IO_L24_35_SPI_DO") (class "Default")
      (node (ref "U1") (pin "F12") (pinfunction "IO_L1P_T0_AD0P_35_F12") (pintype "bidirectional"))
    )
    (net (code "32") (name "/PL_GPIO0") (class "Default")
      (node (ref "TP2") (pin "TP") (pinfunction "TP_TP") (pintype "passive"))
      (node (ref "U1") (pin "K13") (pinfunction "IO_L10P_T1_34_K13") (pintype "bidirectional"))
    )
    (net (code "33") (name "/PL_GPIO1") (class "Default")
      (node (ref "TP4") (pin "TP") (pinfunction "TP_TP") (pintype "passive"))
      (node (ref "U1") (pin "M12") (pinfunction "IO_L12N_T1_MRCC_34_M12") (pintype "bidirectional"))
    )
    (net (code "34") (name "/PL_GPIO2") (class "Default")
      (node (ref "TP6") (pin "TP") (pinfunction "TP_TP") (pintype "passive"))
      (node (ref "U1") (pin "R10") (pinfunction "IO_L24N_T3_34_R10") (pintype "bidirectional"))
    )
    (net (code "35") (name "/PL_GPIO3") (class "Default")
      (node (ref "TP12") (pin "TP") (pinfunction "TP_TP") (pintype "passive"))
      (node (ref "U1") (pin "N14") (pinfunction "IO_L7N_T1_34_N14") (pintype "bidirectional"))
    )
    (net (code "36") (name "/PL_GPIO4") (class "Default")
      (node (ref "TP14") (pin "TP") (pinfunction "TP_TP") (pintype "passive"))
      (node (ref "U1") (pin "M14") (pinfunction "IO_L9N_T1_DQS_34_M14") (pintype "bidirectional"))
    )
    (net (code "37") (name "/PS-SRST#") (class "Default")
      (node (ref "R14") (pin "2") (pinfunction "2_2") (pintype "passive"))
      (node (ref "U1") (pin "B11") (pinfunction "PS_SRST_B_501_B11") (pintype "input"))
    )
    (net (code "38") (name "/PS_CLK_500") (class "Default")
      (node (ref "R15") (pin "1") (pinfunction "1_1") (pintype "passive"))
      (node (ref "R15") (pin "2") (pinfunction "2_2") (pintype "passive"))
      (node (ref "U1") (pin "C7") (pinfunction "PS_CLK_500_C7") (pintype "input"))
      (node (ref "Y1") (pin "3") (pinfunction "OUTPUT_3") (pintype "output"))
    )
    (net (code "39") (name "/PS_GPIO0") (class "Default")
      (node (ref "TP1") (pin "TP") (pinfunction "TP_TP") (pintype "passive"))
      (node (ref "U1") (pin "D8") (pinfunction "PS_MIO0_500_D8") (pintype "bidirectional"))
    )
    (net (code "40") (name "/PS_GPIO1") (class "Default")
      (node (ref "TP3") (pin "TP") (pinfunction "TP_TP") (pintype "passive"))
      (node (ref "U1") (pin "B10") (pinfunction "PS_MIO11_500_B10") (pintype "bidirectional"))
    )
    (net (code "41") (name "/PS_GPIO2") (class "Default")
      (node (ref "U1") (pin "D6") (pinfunction "PS_MIO10_500_D6") (pintype "bidirectional"))
    )
    (net (code "42") (name "/PS_GPIO3") (class "Default")
      (node (ref "TP7") (pin "TP") (pinfunction "TP_TP") (pintype "passive"))
      (node (ref "U1") (pin "B5") (pinfunction "PS_MIO9_500_B5") (pintype "bidirectional"))
    )
    (net (code "43") (name "/PS_GPIO4") (class "Default")
      (node (ref "TP9") (pin "TP") (pinfunction "TP_TP") (pintype "passive"))
      (node (ref "U1") (pin "C13") (pinfunction "PS_MIO53_501_C13") (pintype "bidirectional"))
    )
    (net (code "44") (name "/PS_GPIO5") (class "Default")
      (node (ref "TP11") (pin "TP") (pinfunction "TP_TP") (pintype "passive"))
      (node (ref "U1") (pin "D13") (pinfunction "PS_MIO49_501_D13") (pintype "bidirectional"))
    )
    (net (code "45") (name "/PS_GPIO6") (class "Default")
      (node (ref "TP13") (pin "TP") (pinfunction "TP_TP") (pintype "passive"))
      (node (ref "U1") (pin "B12") (pinfunction "PS_MIO48_501_B12") (pintype "bidirectional"))
    )
    (net (code "46") (name "/PS_MIO01_500_QSPI0_SS_B") (class "Default")
      (node (ref "U1") (pin "A5") (pinfunction "PS_MIO1_500_A5") (pintype "bidirectional"))
    )
    (net (code "47") (name "/PS_MIO02_500_QSPI0_IO0") (class "Default")
      (node (ref "U1") (pin "A8") (pinfunction "PS_MIO2_500_A8") (pintype "bidirectional"))
    )
    (net (code "48") (name "/PS_MIO03_500_QSPI0_IO1") (class "Default")
      (node (ref "U1") (pin "A7") (pinfunction "PS_MIO3_500_A7") (pintype "bidirectional"))
    )
    (net (code "49") (name "/PS_MIO04_500_QSPI0_IO2") (class "Default")
      (node (ref "U1") (pin "C8") (pinfunction "PS_MIO4_500_C8") (pintype "bidirectional"))
    )
    (net (code "50") (name "/PS_MIO05_500_QSPI0_IO3") (class "Default")
      (node (ref "P2") (pin "3") (pinfunction "3_3") (pintype "passive"))
      (node (ref "U1") (pin "A9") (pinfunction "PS_MIO5_500_A9") (pintype "bidirectional"))
    )
    (net (code "51") (name "/PS_MIO06_500_QSPI0_SCLK") (class "Default")
      (node (ref "U1") (pin "A10") (pinfunction "PS_MIO6_500_A10") (pintype "bidirectional"))
    )
    (net (code "52") (name "/PS_MIO07_500_USB_RESET_B") (class "Default")
      (node (ref "R18") (pin "2") (pinfunction "2_2") (pintype "passive"))
      (node (ref "U1") (pin "A12") (pinfunction "PS_MIO52_501_A12") (pintype "bidirectional"))
    )
    (net (code "53") (name "/PS_MIO28_501_USB0_D4") (class "Default")
      (node (ref "U1") (pin "A15") (pinfunction "PS_MIO28_501_A15") (pintype "bidirectional"))
    )
    (net (code "54") (name "/PS_MIO29_501_USB0_DIR") (class "Default")
      (node (ref "U1") (pin "D11") (pinfunction "PS_MIO29_501_D11") (pintype "bidirectional"))
    )
    (net (code "55") (name "/PS_MIO30_501_USB0_STP") (class "Default")
      (node (ref "U1") (pin "B15") (pinfunction "PS_MIO30_501_B15") (pintype "bidirectional"))
    )
    (net (code "56") (name "/PS_MIO31_501_USB0_NXT") (class "Default")
      (node (ref "U1") (pin "C12") (pinfunction "PS_MIO31_501_C12") (pintype "bidirectional"))
    )
    (net (code "57") (name "/PS_MIO32_501_USB0_D0") (class "Default")
      (node (ref "U1") (pin "E15") (pinfunction "PS_MIO32_501_E15") (pintype "bidirectional"))
    )
    (net (code "58") (name "/PS_MIO33_501_USB0_D1") (class "Default")
      (node (ref "U1") (pin "C11") (pinfunction "PS_MIO33_501_C11") (pintype "bidirectional"))
    )
    (net (code "59") (name "/PS_MIO34_501_USB0_D2") (class "Default")
      (node (ref "U1") (pin "D15") (pinfunction "PS_MIO34_501_D15") (pintype "bidirectional"))
    )
    (net (code "60") (name "/PS_MIO35_501_USB0_D3") (class "Default")
      (node (ref "U1") (pin "A14") (pinfunction "PS_MIO35_501_A14") (pintype "bidirectional"))
    )
    (net (code "61") (name "/PS_MIO36_501_USB0_CLK") (class "Default")
      (node (ref "U1") (pin "B14") (pinfunction "PS_MIO36_501_B14") (pintype "bidirectional"))
    )
    (net (code "62") (name "/PS_MIO37_501_USB0_D5") (class "Default")
      (node (ref "U1") (pin "C14") (pinfunction "PS_MIO37_501_C14") (pintype "bidirectional"))
    )
    (net (code "63") (name "/PS_MIO38_501_USB0_D6") (class "Default")
      (node (ref "U1") (pin "A13") (pinfunction "PS_MIO38_501_A13") (pintype "bidirectional"))
    )
    (net (code "64") (name "/PS_MIO39_501_USB0_D7") (class "Default")
      (node (ref "U1") (pin "D14") (pinfunction "PS_MIO39_501_D14") (pintype "bidirectional"))
    )
    (net (code "65") (name "/RX_D0_N") (class "Default")
      (node (ref "U1") (pin "H14") (pinfunction "IO_L3N_T0_DQS_34_H14") (pintype "bidirectional"))
    )
    (net (code "66") (name "/RX_D0_P") (class "Default")
      (node (ref "U1") (pin "J13") (pinfunction "IO_L5P_T0_34_J13") (pintype "bidirectional"))
    )
    (net (code "67") (name "/RX_D1_N") (class "Default")
      (node (ref "U1") (pin "G14") (pinfunction "IO_L3P_T0_DQS_PUDC_B_34_G14") (pintype "bidirectional"))
    )
    (net (code "68") (name "/RX_D1_P") (class "Default")
      (node (ref "U1") (pin "H13") (pinfunction "IO_L2N_T0_34_H13") (pintype "bidirectional"))
    )
    (net (code "69") (name "/RX_D2_N") (class "Default")
      (node (ref "U1") (pin "G12") (pinfunction "IO_L2P_T0_34_G12") (pintype "bidirectional"))
    )
    (net (code "70") (name "/RX_D2_P") (class "Default")
      (node (ref "U1") (pin "H12") (pinfunction "IO_L1N_T0_34_H12") (pintype "bidirectional"))
    )
    (net (code "71") (name "/RX_D3_N") (class "Default")
      (node (ref "U1") (pin "G11") (pinfunction "IO_L1P_T0_34_G11") (pintype "bidirectional"))
    )
    (net (code "72") (name "/RX_D3_P") (class "Default")
      (node (ref "U1") (pin "J14") (pinfunction "IO_L5N_T0_34_J14") (pintype "bidirectional"))
    )
    (net (code "73") (name "/RX_D4_N") (class "Default")
      (node (ref "U1") (pin "J15") (pinfunction "IO_L4P_T0_34_J15") (pintype "bidirectional"))
    )
    (net (code "74") (name "/RX_D4_P") (class "Default")
      (node (ref "U1") (pin "K15") (pinfunction "IO_L4N_T0_34_K15") (pintype "bidirectional"))
    )
    (net (code "75") (name "/RX_D5_N") (class "Default")
      (node (ref "U1") (pin "H11") (pinfunction "IO_L6P_T0_34_H11") (pintype "bidirectional"))
    )
    (net (code "76") (name "/RX_D5_P") (class "Default")
      (node (ref "U1") (pin "J11") (pinfunction "IO_L6N_T0_VREF_34_J11") (pintype "bidirectional"))
    )
    (net (code "77") (name "/SRST") (class "Default")
      (node (ref "J1") (pin "14") (pinfunction "14_14") (pintype "passive"))
      (node (ref "P1") (pin "7") (pinfunction "7_7") (pintype "passive"))
      (node (ref "R10") (pin "2") (pinfunction "2_2") (pintype "passive"))
      (node (ref "R3") (pin "1") (pinfunction "1_1") (pintype "passive"))
    )
    (net (code "78") (name "/Standby") (class "Default")
      (node (ref "Y1") (pin "1") (pinfunction "STANDBY_1") (pintype "input"))
    )
    (net (code "79") (name "/Sys_PG") (class "Default")
      (node (ref "R10") (pin "1") (pinfunction "1_1") (pintype "passive"))
    )
    (net (code "80") (name "/TCK") (class "Default")
      (node (ref "J1") (pin "06") (pinfunction "06_06") (pintype "passive"))
      (node (ref "P1") (pin "3") (pinfunction "3_3") (pintype "passive"))
      (node (ref "R6") (pin "1") (pinfunction "1_1") (pintype "passive"))
      (node (ref "U1") (pin "G9") (pinfunction "TCK_0_G9") (pintype "input"))
    )
    (net (code "81") (name "/TDI") (class "Default")
      (node (ref "J1") (pin "10") (pinfunction "10_10") (pintype "passive"))
      (node (ref "P1") (pin "5") (pinfunction "5_5") (pintype "passive"))
      (node (ref "R4") (pin "1") (pinfunction "1_1") (pintype "passive"))
      (node (ref "U1") (pin "L7") (pinfunction "TDI_0_L7") (pintype "input"))
    )
    (net (code "82") (name "/TDO") (class "Default")
      (node (ref "J1") (pin "08") (pinfunction "08_08") (pintype "passive"))
      (node (ref "P1") (pin "4") (pinfunction "4_4") (pintype "passive"))
      (node (ref "R5") (pin "1") (pinfunction "1_1") (pintype "passive"))
      (node (ref "U1") (pin "L8") (pinfunction "TDO_0_L8") (pintype "output"))
    )
    (net (code "83") (name "/TMS") (class "Default")
      (node (ref "J1") (pin "04") (pinfunction "04_04") (pintype "passive"))
      (node (ref "P1") (pin "2") (pinfunction "2_2") (pintype "passive"))
      (node (ref "R7") (pin "1") (pinfunction "1_1") (pintype "passive"))
      (node (ref "U1") (pin "L9") (pinfunction "TMS_0_L9") (pintype "input"))
    )
    (net (code "84") (name "/TX_D0_N") (class "Default")
      (node (ref "U1") (pin "P15") (pinfunction "IO_L15P_T2_DQS_34_P15") (pintype "bidirectional"))
    )
    (net (code "85") (name "/TX_D0_P") (class "Default")
      (node (ref "U1") (pin "R13") (pinfunction "IO_L17N_T2_34_R13") (pintype "bidirectional"))
    )
    (net (code "86") (name "/TX_D1_N") (class "Default")
      (node (ref "U1") (pin "R15") (pinfunction "IO_L15N_T2_DQS_34_R15") (pintype "bidirectional"))
    )
    (net (code "87") (name "/TX_D1_P") (class "Default")
      (node (ref "U1") (pin "P11") (pinfunction "IO_L16P_T2_34_P11") (pintype "bidirectional"))
    )
    (net (code "88") (name "/TX_D2_N") (class "Default")
      (node (ref "U1") (pin "R11") (pinfunction "IO_L16N_T2_34_R11") (pintype "bidirectional"))
    )
    (net (code "89") (name "/TX_D2_P") (class "Default")
      (node (ref "U1") (pin "R12") (pinfunction "IO_L17P_T2_34_R12") (pintype "bidirectional"))
    )
    (net (code "90") (name "/TX_D3_N") (class "Default")
      (node (ref "U1") (pin "P14") (pinfunction "IO_L18N_T2_34_P14") (pintype "bidirectional"))
    )
    (net (code "91") (name "/TX_D3_P") (class "Default")
      (node (ref "U1") (pin "P13") (pinfunction "IO_L18P_T2_34_P13") (pintype "bidirectional"))
    )
    (net (code "92") (name "/TX_D4_N") (class "Default")
      (node (ref "U1") (pin "N9") (pinfunction "IO_L19N_T3_VREF_34_N9") (pintype "bidirectional"))
    )
    (net (code "93") (name "/TX_D4_P") (class "Default")
      (node (ref "U1") (pin "M9") (pinfunction "IO_L19P_T3_34_M9") (pintype "bidirectional"))
    )
    (net (code "94") (name "/TX_D5_N") (class "Default")
      (node (ref "U1") (pin "R8") (pinfunction "IO_L20N_T3_34_R8") (pintype "bidirectional"))
    )
    (net (code "95") (name "/TX_D5_P") (class "Default")
      (node (ref "U1") (pin "R7") (pinfunction "IO_L20P_T3_34_R7") (pintype "bidirectional"))
    )
    (net (code "96") (name "/UART_RX@ZYNQ") (class "Default")
      (node (ref "P2") (pin "1") (pinfunction "1_1") (pintype "passive"))
      (node (ref "U1") (pin "C6") (pinfunction "PS_MIO13_500_C6") (pintype "bidirectional"))
    )
    (net (code "97") (name "/UART_TX@ZYNQ") (class "Default")
      (node (ref "P2") (pin "2") (pinfunction "2_2") (pintype "passive"))
      (node (ref "U1") (pin "B7") (pinfunction "PS_MIO12_500_B7") (pintype "bidirectional"))
    )
    (net (code "100") (name "/USR_BTN") (class "Default")
      (node (ref "R19") (pin "2") (pinfunction "2_2") (pintype "passive"))
      (node (ref "S1") (pin "1") (pinfunction "1_1") (pintype "passive"))
      (node (ref "S1") (pin "2") (pinfunction "2_2") (pintype "passive"))
      (node (ref "U1") (pin "B9") (pinfunction "PS_MIO14_500_B9") (pintype "bidirectional"))
    )
    (net (code "101") (name "/USR_LED") (class "Default")
      (node (ref "U1") (pin "D10") (pinfunction "PS_MIO15_500_D10") (pintype "bidirectional"))
      (node (ref "U3") (pin "1") (pinfunction "GATE_1") (pintype "passive"))
    )
    (net (code "102") (name "/VMODE_0") (class "Default")
      (node (ref "R16") (pin "2") (pinfunction "2_2") (pintype "passive"))
      (node (ref "U1") (pin "D9") (pinfunction "PS_MIO7_500_D9") (pintype "bidirectional"))
    )
    (net (code "103") (name "/VMODE_1") (class "Default")
      (node (ref "R17") (pin "2") (pinfunction "2_2") (pintype "passive"))
      (node (ref "U1") (pin "B6") (pinfunction "PS_MIO8_500_B6") (pintype "bidirectional"))
    )
    (net (code "110") (name "1.35V") (class "Default")
      (node (ref "C35") (pin "1") (pinfunction "1_1") (pintype "passive"))
      (node (ref "C36") (pin "1") (pinfunction "1_1") (pintype "passive"))
      (node (ref "C37") (pin "1") (pinfunction "1_1") (pintype "passive"))
      (node (ref "C38") (pin "1") (pinfunction "1_1") (pintype "passive"))
      (node (ref "C39") (pin "1") (pinfunction "1_1") (pintype "passive"))
      (node (ref "C40") (pin "1") (pinfunction "1_1") (pintype "passive"))
      (node (ref "C41") (pin "1") (pinfunction "1_1") (pintype "passive"))
      (node (ref "C42") (pin "1") (pinfunction "1_1") (pintype "passive"))
      (node (ref "C43") (pin "2") (pinfunction "2_2") (pintype "passive"))
      (node (ref "U1") (pin "B3") (pinfunction "VCCO_DDR_502_B3") (pintype "power_in"))
      (node (ref "U1") (pin "E4") (pinfunction "VCCO_DDR_502_E4") (pintype "power_in"))
      (node (ref "U1") (pin "F1") (pinfunction "VCCO_DDR_502_F1") (pintype "power_in"))
      (node (ref "U1") (pin "J2") (pinfunction "VCCO_DDR_502_J2") (pintype "power_in"))
      (node (ref "U1") (pin "M3") (pinfunction "VCCO_DDR_502_M3") (pintype "power_in"))
      (node (ref "U1") (pin "R4") (pinfunction "VCCO_DDR_502_R4") (pintype "power_in"))
    )
    (net (code "111") (name "5V") (class "Default")
      (node (ref "D1") (pin "A") (pinfunction "A_A") (pintype "passive"))
      (node (ref "D2") (pin "A") (pinfunction "A_A") (pintype "passive"))
    )
    (net (code "112") (name "GND") (class "Default")
      (node (ref "C1") (pin "2") (pinfunction "2_2") (pintype "passive"))
      (node (ref "C12") (pin "2") (pinfunction "2_2") (pintype "passive"))
      (node (ref "C13") (pin "2") (pinfunction "2_2") (pintype "passive"))
      (node (ref "C14") (pin "2") (pinfunction "2_2") (pintype "passive"))
      (node (ref "C15") (pin "2") (pinfunction "2_2") (pintype "passive"))
      (node (ref "C16") (pin "2") (pinfunction "2_2") (pintype "passive"))
      (node (ref "C17") (pin "2") (pinfunction "2_2") (pintype "passive"))
      (node (ref "C18") (pin "1") (pinfunction "1_1") (pintype "passive"))
      (node (ref "C2") (pin "2") (pinfunction "2_2") (pintype "passive"))
      (node (ref "C21") (pin "2") (pinfunction "2_2") (pintype "passive"))
      (node (ref "C22") (pin "2") (pinfunction "2_2") (pintype "passive"))
      (node (ref "C23") (pin "2") (pinfunction "2_2") (pintype "passive"))
      (node (ref "C24") (pin "2") (pinfunction "2_2") (pintype "passive"))
      (node (ref "C25") (pin "2") (pinfunction "2_2") (pintype "passive"))
      (node (ref "C26") (pin "1") (pinfunction "1_1") (pintype "passive"))
      (node (ref "C27") (pin "2") (pinfunction "2_2") (pintype "passive"))
      (node (ref "C28") (pin "2") (pinfunction "2_2") (pintype "passive"))
      (node (ref "C29") (pin "2") (pinfunction "2_2") (pintype "passive"))
      (node (ref "C3") (pin "2") (pinfunction "2_2") (pintype "passive"))
      (node (ref "C30") (pin "2") (pinfunction "2_2") (pintype "passive"))
      (node (ref "C31") (pin "1") (pinfunction "1_1") (pintype "passive"))
      (node (ref "C32") (pin "2") (pinfunction "2_2") (pintype "passive"))
      (node (ref "C33") (pin "2") (pinfunction "2_2") (pintype "passive"))
      (node (ref "C34") (pin "2") (pinfunction "2_2") (pintype "passive"))
      (node (ref "C37") (pin "2") (pinfunction "2_2") (pintype "passive"))
      (node (ref "C4") (pin "1") (pinfunction "1_1") (pintype "passive"))
      (node (ref "C5") (pin "2") (pinfunction "2_2") (pintype "passive"))
      (node (ref "C6") (pin "2") (pinfunction "2_2") (pintype "passive"))
      (node (ref "C7") (pin "2") (pinfunction "2_2") (pintype "passive"))
      (node (ref "C8") (pin "2") (pinfunction "2_2") (pintype "passive"))
      (node (ref "C9") (pin "1") (pinfunction "1_1") (pintype "passive"))
      (node (ref "FB2") (pin "1") (pintype "passive"))
      (node (ref "J1") (pin "01") (pinfunction "01_01") (pintype "passive"))
      (node (ref "J1") (pin "03") (pinfunction "03_03") (pintype "passive"))
      (node (ref "J1") (pin "05") (pinfunction "05_05") (pintype "passive"))
      (node (ref "J1") (pin "07") (pinfunction "07_07") (pintype "passive"))
      (node (ref "J1") (pin "09") (pinfunction "09_09") (pintype "passive"))
      (node (ref "J1") (pin "11") (pinfunction "11_11") (pintype "passive"))
      (node (ref "J1") (pin "13") (pinfunction "13_13") (pintype "passive"))
      (node (ref "P1") (pin "6") (pinfunction "6_6") (pintype "passive"))
      (node (ref "P2") (pin "4") (pinfunction "4_4") (pintype "passive"))
      (node (ref "P2") (pin "5") (pinfunction "5_5") (pintype "passive"))
      (node (ref "P2") (pin "6") (pinfunction "6_6") (pintype "passive"))
      (node (ref "P2") (pin "7") (pinfunction "7_7") (pintype "passive"))
      (node (ref "R11") (pin "1") (pinfunction "1_1") (pintype "passive"))
      (node (ref "R12") (pin "1") (pinfunction "1_1") (pintype "passive"))
      (node (ref "S1") (pin "3") (pinfunction "3_3") (pintype "passive"))
      (node (ref "S1") (pin "4") (pinfunction "4_4") (pintype "passive"))
      (node (ref "TP10") (pin "TP") (pinfunction "TP_TP") (pintype "passive"))
      (node (ref "TP15") (pin "TP") (pinfunction "TP_TP") (pintype "passive"))
      (node (ref "U1") (pin "A1") (pinfunction "GND_A1") (pintype "power_in"))
      (node (ref "U1") (pin "A11") (pinfunction "GND_A11") (pintype "power_in"))
      (node (ref "U1") (pin "B8") (pinfunction "GND_B8") (pintype "power_in"))
      (node (ref "U1") (pin "C15") (pinfunction "GND_C15") (pintype "power_in"))
      (node (ref "U1") (pin "C5") (pinfunction "GND_C5") (pintype "power_in"))
      (node (ref "U1") (pin "D12") (pinfunction "GND_D12") (pintype "power_in"))
      (node (ref "U1") (pin "D2") (pinfunction "GND_D2") (pintype "power_in"))
      (node (ref "U1") (pin "E5") (pinfunction "GND_E5") (pintype "power_in"))
      (node (ref "U1") (pin "E7") (pinfunction "GND_E7") (pintype "power_in"))
      (node (ref "U1") (pin "E8") (pinfunction "RSVDGND_E8") (pintype "passive"))
      (node (ref "U1") (pin "E9") (pinfunction "GND_E9") (pintype "power_in"))
      (node (ref "U1") (pin "F10") (pinfunction "GND_F10") (pintype "power_in"))
      (node (ref "U1") (pin "G13") (pinfunction "GND_G13") (pintype "power_in"))
      (node (ref "U1") (pin "G3") (pinfunction "GND_G3") (pintype "power_in"))
      (node (ref "U1") (pin "G5") (pinfunction "GND_G5") (pintype "power_in"))
      (node (ref "U1") (pin "H10") (pinfunction "GND_H10") (pintype "power_in"))
      (node (ref "U1") (pin "H6") (pinfunction "GND_H6") (pintype "power_in"))
      (node (ref "U1") (pin "H8") (pinfunction "VN_0_H8") (pintype "input"))
      (node (ref "U1") (pin "J5") (pinfunction "GND_J5") (pintype "power_in"))
      (node (ref "U1") (pin "J9") (pinfunction "GND_J9") (pintype "power_in"))
      (node (ref "U1") (pin "K10") (pinfunction "GND_K10") (pintype "power_in"))
      (node (ref "U1") (pin "K14") (pinfunction "GND_K14") (pintype "power_in"))
      (node (ref "U1") (pin "K4") (pinfunction "GND_K4") (pintype "power_in"))
      (node (ref "U1") (pin "K7") (pinfunction "GND_K7") (pintype "power_in"))
      (node (ref "U1") (pin "L1") (pinfunction "GND_L1") (pintype "power_in"))
      (node (ref "U1") (pin "L11") (pinfunction "GND_L11") (pintype "power_in"))
      (node (ref "U1") (pin "L5") (pinfunction "GND_L5") (pintype "power_in"))
      (node (ref "U1") (pin "M8") (pinfunction "GND_M8") (pintype "power_in"))
      (node (ref "U1") (pin "N15") (pinfunction "GND_N15") (pintype "power_in"))
      (node (ref "U1") (pin "N5") (pinfunction "GND_N5") (pintype "power_in"))
      (node (ref "U1") (pin "P12") (pinfunction "GND_P12") (pintype "power_in"))
      (node (ref "U1") (pin "P2") (pinfunction "GND_P2") (pintype "power_in"))
      (node (ref "U1") (pin "R9") (pinfunction "GND_R9") (pintype "power_in"))
      (node (ref "U2") (pin "2") (pinfunction "SOURCE_2") (pintype "passive"))
      (node (ref "U3") (pin "2") (pinfunction "SOURCE_2") (pintype "passive"))
      (node (ref "Y1") (pin "2") (pinfunction "GND_2") (pintype "power_in"))
    )
    (net (code "113") (name "Net-(C19-Pad2)") (class "Default")
      (node (ref "C19") (pin "2") (pinfunction "2_2") (pintype "passive"))
      (node (ref "C20") (pin "2") (pinfunction "2_2") (pintype "passive"))
    )
    (net (code "114") (name "Net-(C35-Pad2)") (class "Default")
      (node (ref "C35") (pin "2") (pinfunction "2_2") (pintype "passive"))
      (node (ref "C36") (pin "2") (pinfunction "2_2") (pintype "passive"))
      (node (ref "C38") (pin "2") (pinfunction "2_2") (pintype "passive"))
      (node (ref "C39") (pin "2") (pinfunction "2_2") (pintype "passive"))
      (node (ref "C40") (pin "2") (pinfunction "2_2") (pintype "passive"))
      (node (ref "C41") (pin "2") (pinfunction "2_2") (pintype "passive"))
      (node (ref "C43") (pin "1") (pinfunction "1_1") (pintype "passive"))
    )
    (net (code "115") (name "Net-(D1-PadC)") (class "Default")
      (node (ref "D1") (pin "C") (pinfunction "C_C") (pintype "passive"))
      (node (ref "R1") (pin "2") (pinfunction "2_2") (pintype "passive"))
    )
    (net (code "116") (name "Net-(D2-PadC)") (class "Default")
      (node (ref "D2") (pin "C") (pinfunction "C_C") (pintype "passive"))
      (node (ref "R20") (pin "2") (pinfunction "2_2") (pintype "passive"))
    )
    (net (code "117") (name "Net-(R16-Pad1)") (class "Default")
      (node (ref "R16") (pin "1") (pinfunction "1_1") (pintype "passive"))
      (node (ref "R17") (pin "1") (pinfunction "1_1") (pintype "passive"))
    )
    (net (code "118") (name "Net-(U1A-CFGBVS_0)") (class "Default")
      (node (ref "C10") (pin "2") (pinfunction "2_2") (pintype "passive"))
      (node (ref "C11") (pin "2") (pinfunction "2_2") (pintype "passive"))
      (node (ref "FB2") (pin "2") (pintype "passive"))
      (node (ref "U1") (pin "F6") (pinfunction "CFGBVS_0_F6") (pintype "input"))
      (node (ref "U1") (pin "F8") (pinfunction "GNDADC_0_F8") (pintype "power_in"))
      (node (ref "U1") (pin "G8") (pinfunction "VREFN_0_G8") (pintype "power_in"))
      (node (ref "U1") (pin "H7") (pinfunction "VREFP_0_H7") (pintype "power_in"))
      (node (ref "U1") (pin "J7") (pinfunction "DXP_0_J7") (pintype "output"))
    )
    (net (code "119") (name "Net-(U1A-DONE_0)") (class "Default")
      (node (ref "U1") (pin "M7") (pinfunction "DONE_0_M7") (pintype "bidirectional"))
      (node (ref "U2") (pin "1") (pinfunction "GATE_1") (pintype "passive"))
    )
    (net (code "120") (name "Net-(U1A-INIT_B_0)") (class "Default")
      (node (ref "R2") (pin "1") (pinfunction "1_1") (pintype "passive"))
      (node (ref "U1") (pin "D5") (pinfunction "INIT_B_0_D5") (pintype "bidirectional"))
    )
    (net (code "121") (name "Net-(U1A-PROGRAM_B_0)") (class "Default")
      (node (ref "R8") (pin "1") (pinfunction "1_1") (pintype "passive"))
      (node (ref "U1") (pin "K6") (pinfunction "PROGRAM_B_0_K6") (pintype "input"))
    )
    (net (code "122") (name "Net-(U1A-VP_0)") (class "Default")
      (node (ref "R11") (pin "2") (pinfunction "2_2") (pintype "passive"))
      (node (ref "R12") (pin "2") (pinfunction "2_2") (pintype "passive"))
      (node (ref "R9") (pin "1") (pinfunction "1_1") (pintype "passive"))
      (node (ref "U1") (pin "G7") (pinfunction "VP_0_G7") (pintype "input"))
    )
    (net (code "123") (name "Net-(U1D-PS_POR_B_500)") (class "Default")
      (node (ref "R13") (pin "2") (pinfunction "2_2") (pintype "passive"))
      (node (ref "U1") (pin "C9") (pinfunction "PS_POR_B_500_C9") (pintype "input"))
    )
    (net (code "124") (name "Net-(U2-DRAIN)") (class "Default")
      (node (ref "R1") (pin "1") (pinfunction "1_1") (pintype "passive"))
      (node (ref "U2") (pin "3") (pinfunction "DRAIN_3") (pintype "passive"))
    )
    (net (code "125") (name "Net-(U3-DRAIN)") (class "Default")
      (node (ref "R20") (pin "1") (pinfunction "1_1") (pintype "passive"))
      (node (ref "U3") (pin "3") (pinfunction "DRAIN_3") (pintype "passive"))
    )
    (net (code "126") (name "VCCP_AUX") (class "Default")
      (node (ref "C16") (pin "1") (pinfunction "1_1") (pintype "passive"))
      (node (ref "C17") (pin "1") (pinfunction "1_1") (pintype "passive"))
      (node (ref "C18") (pin "2") (pinfunction "2_2") (pintype "passive"))
      (node (ref "FB3") (pin "1") (pintype "passive"))
    )
    (net (code "127") (name "VCCP_INT") (class "Default")
      (node (ref "C1") (pin "1") (pinfunction "1_1") (pintype "passive"))
      (node (ref "C2") (pin "1") (pinfunction "1_1") (pintype "passive"))
      (node (ref "C3") (pin "1") (pinfunction "1_1") (pintype "passive"))
      (node (ref "C4") (pin "2") (pinfunction "2_2") (pintype "passive"))
      (node (ref "C5") (pin "1") (pinfunction "1_1") (pintype "passive"))
      (node (ref "C6") (pin "1") (pinfunction "1_1") (pintype "passive"))
      (node (ref "C7") (pin "1") (pinfunction "1_1") (pintype "passive"))
      (node (ref "C8") (pin "1") (pinfunction "1_1") (pintype "passive"))
      (node (ref "C9") (pin "2") (pinfunction "2_2") (pintype "passive"))
      (node (ref "U1") (pin "E10") (pinfunction "VCCINT_E10") (pintype "power_in"))
      (node (ref "U1") (pin "F9") (pinfunction "VCCINT_F9") (pintype "power_in"))
      (node (ref "U1") (pin "G10") (pinfunction "VCCINT_G10") (pintype "power_in"))
      (node (ref "U1") (pin "G6") (pinfunction "VCCPINT_G6") (pintype "power_in"))
      (node (ref "U1") (pin "H5") (pinfunction "VCCPINT_H5") (pintype "power_in"))
      (node (ref "U1") (pin "J10") (pinfunction "VCCINT_J10") (pintype "power_in"))
      (node (ref "U1") (pin "K5") (pinfunction "VCCPINT_K5") (pintype "power_in"))
      (node (ref "U1") (pin "L10") (pinfunction "VCCINT_L10") (pintype "power_in"))
    )
    (net (code "128") (name "VCC_0_PL") (class "Default")
      (node (ref "U1") (pin "G4") (pinfunction "RSVSVCC1_G4") (pintype "passive"))
      (node (ref "U1") (pin "H4") (pinfunction "RSVSVCC3_H4") (pintype "passive"))
      (node (ref "U1") (pin "J4") (pinfunction "RSVSVCC2_J4") (pintype "passive"))
    )
    (net (code "129") (name "VCC_AUX") (class "Default")
      (node (ref "C13") (pin "1") (pinfunction "1_1") (pintype "passive"))
      (node (ref "C14") (pin "1") (pinfunction "1_1") (pintype "passive"))
      (node (ref "C15") (pin "1") (pinfunction "1_1") (pintype "passive"))
      (node (ref "FB1") (pin "1") (pintype "passive"))
      (node (ref "U1") (pin "H9") (pinfunction "VCCAUX_H9") (pintype "power_in"))
      (node (ref "U1") (pin "J6") (pinfunction "VCCPAUX_J6") (pintype "power_in"))
      (node (ref "U1") (pin "J8") (pinfunction "VCCAUX_J8") (pintype "power_in"))
      (node (ref "U1") (pin "K9") (pinfunction "VCCAUX_K9") (pintype "power_in"))
      (node (ref "U1") (pin "L6") (pinfunction "VCCPAUX_L6") (pintype "power_in"))
    )
    (net (code "130") (name "VCC_PLL") (class "Default")
      (node (ref "C19") (pin "1") (pinfunction "1_1") (pintype "passive"))
      (node (ref "C20") (pin "1") (pinfunction "1_1") (pintype "passive"))
      (node (ref "FB4") (pin "1") (pintype "passive"))
      (node (ref "U1") (pin "F5") (pinfunction "VCCPLL_F5") (pintype "power_in"))
    )
    (net (code "131") (name "VDDIO_0_PL") (class "Default")
      (node (ref "C32") (pin "1") (pinfunction "1_1") (pintype "passive"))
      (node (ref "FB8") (pin "1") (pintype "passive"))
      (node (ref "J1") (pin "02") (pinfunction "02_02") (pintype "passive"))
      (node (ref "P1") (pin "1") (pinfunction "1_1") (pintype "passive"))
      (node (ref "R2") (pin "2") (pinfunction "2_2") (pintype "passive"))
      (node (ref "R3") (pin "2") (pinfunction "2_2") (pintype "passive"))
      (node (ref "R4") (pin "2") (pinfunction "2_2") (pintype "passive"))
      (node (ref "R5") (pin "2") (pinfunction "2_2") (pintype "passive"))
      (node (ref "R6") (pin "2") (pinfunction "2_2") (pintype "passive"))
      (node (ref "R7") (pin "2") (pinfunction "2_2") (pintype "passive"))
      (node (ref "R8") (pin "2") (pinfunction "2_2") (pintype "passive"))
      (node (ref "U1") (pin "K8") (pinfunction "VCCO_0_K8") (pintype "power_in"))
    )
    (net (code "132") (name "VDDIO_34_PL") (class "Default")
      (node (ref "FB9") (pin "1") (pintype "passive"))
      (node (ref "U1") (pin "J12") (pinfunction "VCCO_34_J12") (pintype "power_in"))
      (node (ref "U1") (pin "M13") (pinfunction "VCCO_34_M13") (pintype "power_in"))
      (node (ref "U1") (pin "N10") (pinfunction "VCCO_34_N10") (pintype "power_in"))
      (node (ref "U1") (pin "P7") (pinfunction "VCCO_34_P7") (pintype "power_in"))
      (node (ref "U1") (pin "R14") (pinfunction "VCCO_34_R14") (pintype "power_in"))
    )
    (net (code "133") (name "VDDIO_35_PL") (class "Default")
      (node (ref "FB10") (pin "1") (pintype "passive"))
      (node (ref "U1") (pin "F11") (pinfunction "VCCO_35_F11") (pintype "power_in"))
      (node (ref "U1") (pin "H15") (pinfunction "VCCO_35_H15") (pintype "power_in"))
    )
    (net (code "134") (name "VDDIO_500_PS") (class "Default")
      (node (ref "C28") (pin "1") (pinfunction "1_1") (pintype "passive"))
      (node (ref "C29") (pin "1") (pinfunction "1_1") (pintype "passive"))
      (node (ref "C30") (pin "1") (pinfunction "1_1") (pintype "passive"))
      (node (ref "C31") (pin "2") (pinfunction "2_2") (pintype "passive"))
      (node (ref "C34") (pin "1") (pinfunction "1_1") (pintype "passive"))
      (node (ref "FB7") (pin "1") (pintype "passive"))
      (node (ref "R13") (pin "1") (pinfunction "1_1") (pintype "passive"))
      (node (ref "U1") (pin "A6") (pinfunction "VCCO_MIO0_500_A6") (pintype "power_in"))
      (node (ref "U1") (pin "D7") (pinfunction "VCCO_MIO0_500_D7") (pintype "power_in"))
      (node (ref "Y1") (pin "4") (pinfunction "VDD_4") (pintype "power_in"))
    )
    (net (code "135") (name "VDDIO_501_PS") (class "Default")
      (node (ref "C23") (pin "1") (pinfunction "1_1") (pintype "passive"))
      (node (ref "C24") (pin "1") (pinfunction "1_1") (pintype "passive"))
      (node (ref "C25") (pin "1") (pinfunction "1_1") (pintype "passive"))
      (node (ref "C26") (pin "2") (pinfunction "2_2") (pintype "passive"))
      (node (ref "FB5") (pin "1") (pintype "passive"))
      (node (ref "R14") (pin "1") (pinfunction "1_1") (pintype "passive"))
      (node (ref "R18") (pin "1") (pinfunction "1_1") (pintype "passive"))
      (node (ref "U1") (pin "B13") (pinfunction "VCCO_MIO1_501_B13") (pintype "power_in"))
      (node (ref "U1") (pin "C10") (pinfunction "VCCO_MIO1_501_C10") (pintype "power_in"))
      (node (ref "U1") (pin "E14") (pinfunction "VCCO_MIO1_501_E14") (pintype "power_in"))
    )
    (net (code "136") (name "VDD_1.8V") (class "Default")
      (node (ref "C21") (pin "1") (pinfunction "1_1") (pintype "passive"))
      (node (ref "FB1") (pin "2") (pintype "passive"))
      (node (ref "FB10") (pin "2") (pintype "passive"))
      (node (ref "FB3") (pin "2") (pintype "passive"))
      (node (ref "FB4") (pin "2") (pintype "passive"))
      (node (ref "FB5") (pin "2") (pintype "passive"))
      (node (ref "FB6") (pin "2") (pintype "passive"))
      (node (ref "FB7") (pin "2") (pintype "passive"))
      (node (ref "FB8") (pin "2") (pintype "passive"))
      (node (ref "FB9") (pin "2") (pintype "passive"))
      (node (ref "R19") (pin "1") (pinfunction "1_1") (pintype "passive"))
      (node (ref "TP8") (pin "TP") (pinfunction "TP_TP") (pintype "passive"))
      (node (ref "U1") (pin "E6") (pinfunction "VCCBATT_0_E6") (pintype "power_in"))
    )
    (net (code "137") (name "XADC_VCC") (class "Default")
      (node (ref "C10") (pin "1") (pinfunction "1_1") (pintype "passive"))
      (node (ref "C11") (pin "1") (pinfunction "1_1") (pintype "passive"))
      (node (ref "C12") (pin "1") (pinfunction "1_1") (pintype "passive"))
      (node (ref "FB6") (pin "1") (pintype "passive"))
      (node (ref "R9") (pin "2") (pinfunction "2_2") (pintype "passive"))
      (node (ref "U1") (pin "F7") (pinfunction "VCCADC_0_F7") (pintype "power_in"))
    )
    (net (code "138") (name "unconnected-(C22-Pad1)") (class "Default")
      (node (ref "C22") (pin "1") (pinfunction "1_1") (pintype "passive"))
    )
    (net (code "139") (name "unconnected-(C27-Pad1)") (class "Default")
      (node (ref "C27") (pin "1") (pinfunction "1_1") (pintype "passive"))
    )
    (net (code "140") (name "unconnected-(C33-Pad1)") (class "Default")
      (node (ref "C33") (pin "1") (pinfunction "1_1") (pintype "passive"))
    )
    (net (code "141") (name "unconnected-(C42-Pad2)") (class "Default")
      (node (ref "C42") (pin "2") (pinfunction "2_2") (pintype "passive"))
    )
    (net (code "142") (name "unconnected-(J1-Pad12)") (class "Default")
      (node (ref "J1") (pin "12") (pinfunction "12_12") (pintype "passive"))
    )
    (net (code "143") (name "unconnected-(S1-SHIELD-Pad5)") (class "Default")
      (node (ref "S1") (pin "5") (pinfunction "SHIELD_5") (pintype "passive"))
    )
    (net (code "144") (name "unconnected-(TP5-PadTP)") (class "Default")
      (node (ref "TP5") (pin "TP") (pinfunction "TP_TP") (pintype "passive"))
    )
  )
)
